# CrawlerSch26_04_22_2.net
KiCad netlist of a schematic drawn in Altium Designer
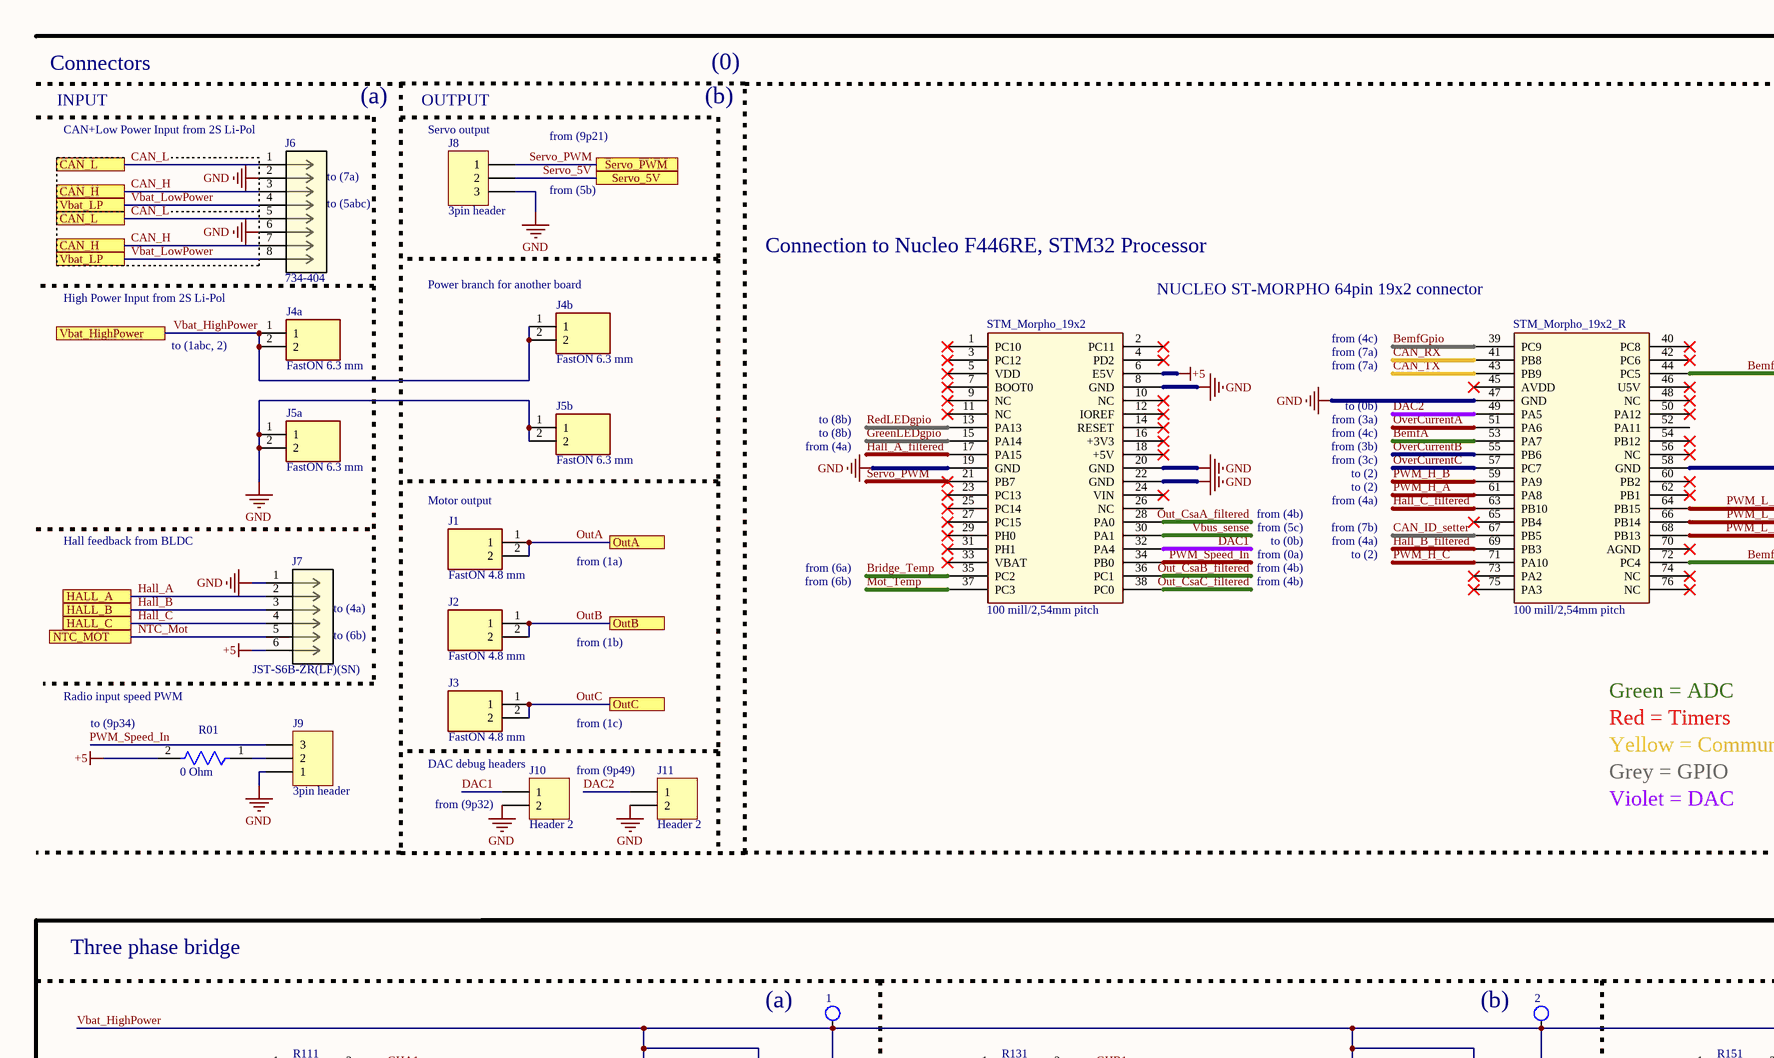
[diagram p0: CrawlerSch26_04_22 2.SchDoc, top left]
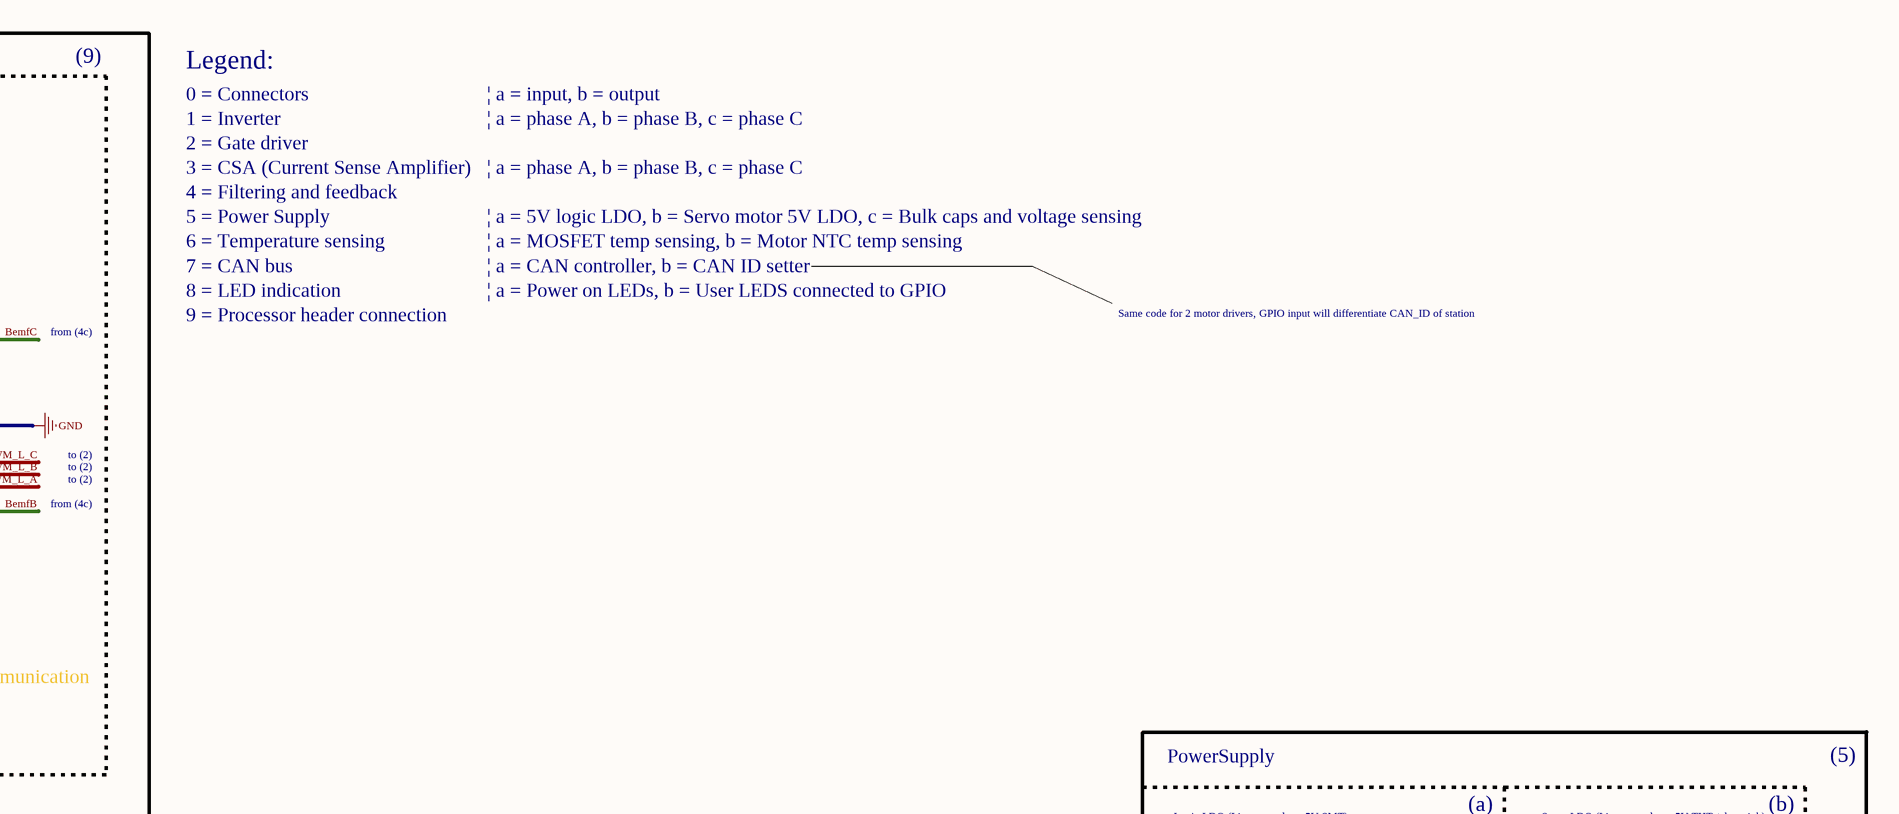
[diagram p1: CrawlerSch26_04_22 2.SchDoc, top right]
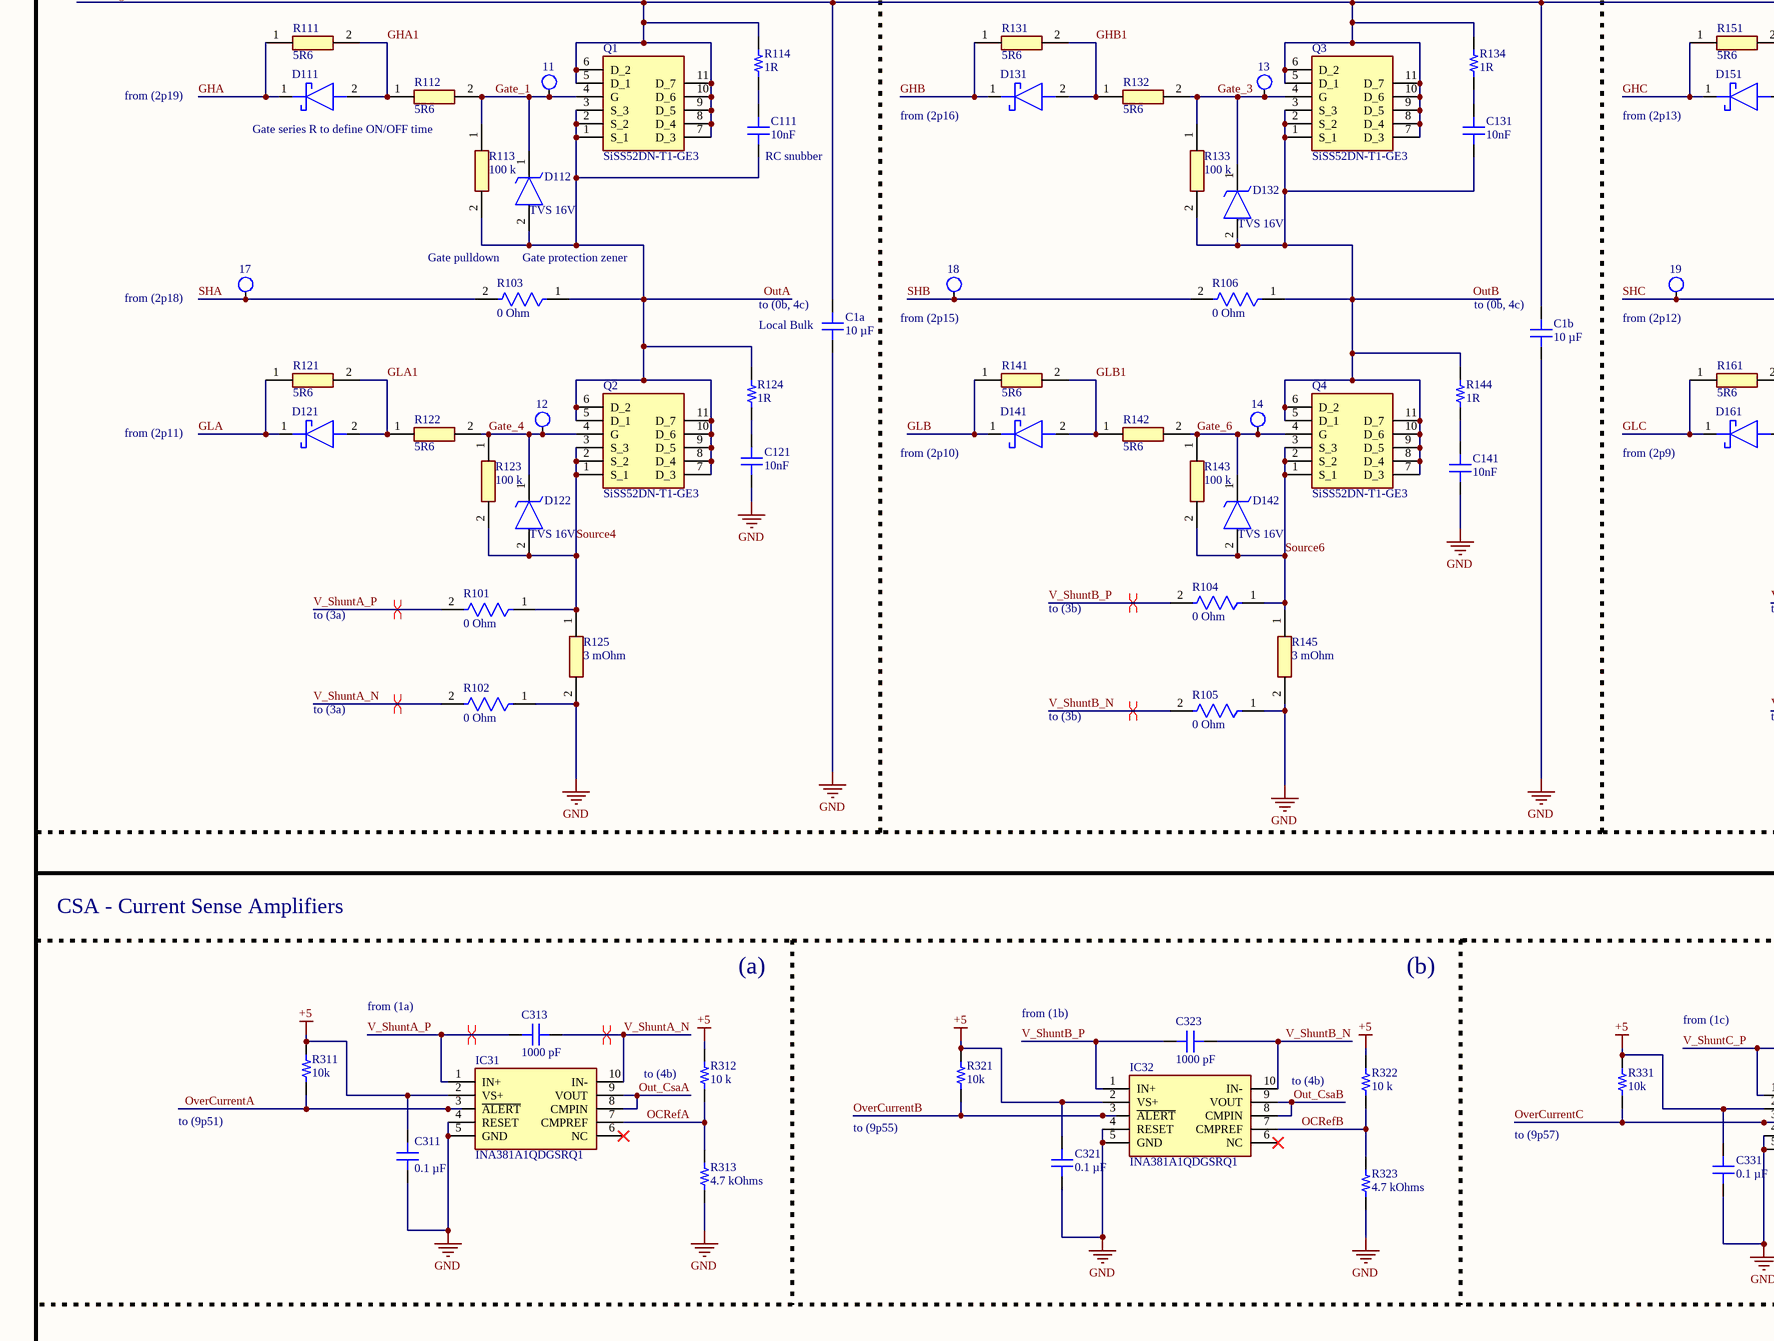
[diagram p2: CrawlerSch26_04_22 2.SchDoc, bottom left]
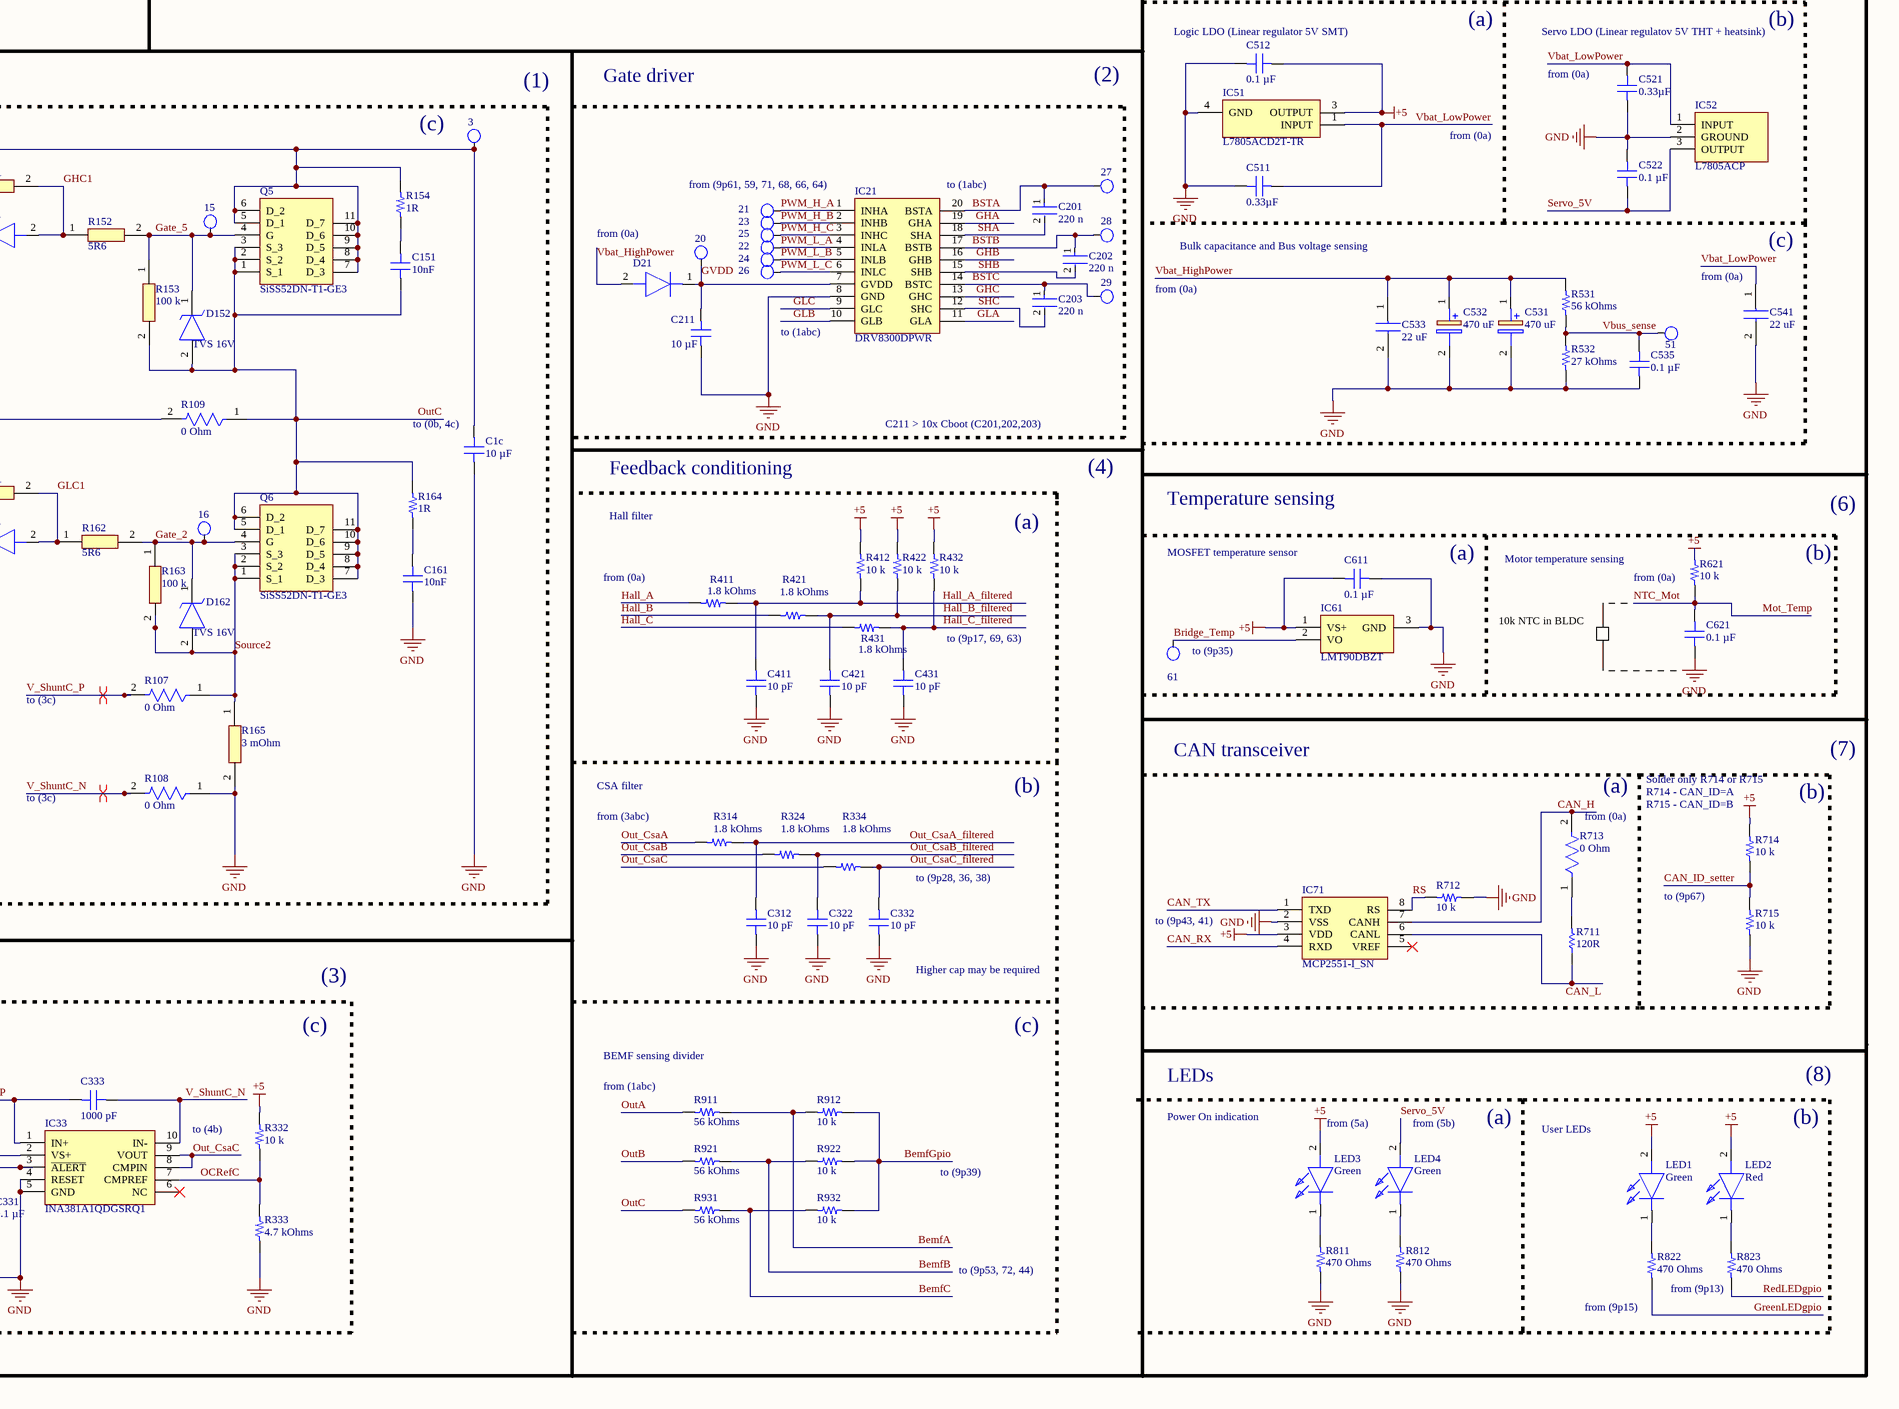
[diagram p3: CrawlerSch26_04_22 2.SchDoc, bottom right]

(export (version "E")
  (design (tool "Eeschema 10.0.6"))
  (components
    (comp (ref "1")
      (value "TestPad")
      (footprint "TestPad")
      (libsource (lib "MyLib_Crawler") (part "TestPad"))
    )
    (comp (ref "2")
      (value "TestPad")
      (footprint "TestPad")
      (libsource (lib "MyLib_Crawler") (part "TestPad"))
    )
    (comp (ref "3")
      (value "TestPad")
      (footprint "TestPad")
      (libsource (lib "MyLib_Crawler") (part "TestPad"))
    )
    (comp (ref "11")
      (value "TestPad")
      (footprint "TestPad")
      (libsource (lib "MyLib_Crawler") (part "TestPad"))
    )
    (comp (ref "12")
      (value "TestPad")
      (footprint "TestPad")
      (libsource (lib "MyLib_Crawler") (part "TestPad"))
    )
    (comp (ref "13")
      (value "TestPad")
      (footprint "TestPad")
      (libsource (lib "MyLib_Crawler") (part "TestPad"))
    )
    (comp (ref "14")
      (value "TestPad")
      (footprint "TestPad")
      (libsource (lib "MyLib_Crawler") (part "TestPad"))
    )
    (comp (ref "15")
      (value "TestPad")
      (footprint "TestPad")
      (libsource (lib "MyLib_Crawler") (part "TestPad"))
    )
    (comp (ref "16")
      (value "TestPad")
      (footprint "TestPad")
      (libsource (lib "MyLib_Crawler") (part "TestPad"))
    )
    (comp (ref "17")
      (value "TestPad")
      (footprint "TestPad")
      (libsource (lib "MyLib_Crawler") (part "TestPad"))
    )
    (comp (ref "18")
      (value "TestPad")
      (footprint "TestPad")
      (libsource (lib "MyLib_Crawler") (part "TestPad"))
    )
    (comp (ref "19")
      (value "TestPad")
      (footprint "TestPad")
      (libsource (lib "MyLib_Crawler") (part "TestPad"))
    )
    (comp (ref "20")
      (value "TestPad")
      (footprint "TestPad")
      (libsource (lib "MyLib_Crawler") (part "TestPad"))
    )
    (comp (ref "21")
      (value "TestPad")
      (footprint "TestPad")
      (libsource (lib "MyLib_Crawler") (part "TestPad"))
    )
    (comp (ref "22")
      (value "TestPad")
      (footprint "TestPad")
      (libsource (lib "MyLib_Crawler") (part "TestPad"))
    )
    (comp (ref "23")
      (value "TestPad")
      (footprint "TestPad")
      (libsource (lib "MyLib_Crawler") (part "TestPad"))
    )
    (comp (ref "24")
      (value "TestPad")
      (footprint "TestPad")
      (libsource (lib "MyLib_Crawler") (part "TestPad"))
    )
    (comp (ref "25")
      (value "TestPad")
      (footprint "TestPad")
      (libsource (lib "MyLib_Crawler") (part "TestPad"))
    )
    (comp (ref "26")
      (value "TestPad")
      (footprint "TestPad")
      (libsource (lib "MyLib_Crawler") (part "TestPad"))
    )
    (comp (ref "27")
      (value "TestPad")
      (footprint "TestPad")
      (libsource (lib "MyLib_Crawler") (part "TestPad"))
    )
    (comp (ref "28")
      (value "TestPad")
      (footprint "TestPad")
      (libsource (lib "MyLib_Crawler") (part "TestPad"))
    )
    (comp (ref "29")
      (value "TestPad")
      (footprint "TestPad")
      (libsource (lib "MyLib_Crawler") (part "TestPad"))
    )
    (comp (ref "51")
      (value "TestPad")
      (footprint "TestPad")
      (libsource (lib "MyLib_Crawler") (part "TestPad"))
    )
    (comp (ref "61")
      (value "TestPad")
      (footprint "TestPad")
      (libsource (lib "MyLib_Crawler") (part "TestPad"))
    )
    (comp (ref "C1a")
      (value "10 µF")
      (footprint "CAP 0805_2012")
      (description "CAP CER 10UF 25V X5R 0805")
      (fields (field (name "PART NUMBER") "TMK212BBJ106KG-T") (field (name "MANUFACTURER") "Taiyo Yuden"))
      (libsource (lib "Celestial Altium Library - altium_library") (part "Capacitor"))
    )
    (comp (ref "C1b")
      (value "10 µF")
      (footprint "CAP 0805_2012")
      (description "CAP CER 10UF 25V X5R 0805")
      (fields (field (name "PART NUMBER") "TMK212BBJ106KG-T") (field (name "MANUFACTURER") "Taiyo Yuden"))
      (libsource (lib "Celestial Altium Library - altium_library") (part "Capacitor"))
    )
    (comp (ref "C1c")
      (value "10 µF")
      (footprint "CAP 0805_2012")
      (description "CAP CER 10UF 25V X5R 0805")
      (fields (field (name "PART NUMBER") "TMK212BBJ106KG-T") (field (name "MANUFACTURER") "Taiyo Yuden"))
      (libsource (lib "Celestial Altium Library - altium_library") (part "Capacitor"))
    )
    (comp (ref "C111")
      (value "10nF")
      (footprint "CAP 0805_2012")
      (description "CAP CER 0805 10NF 50V C0G 5%")
      (fields (field (name "PART NUMBER") "C0805C103J5GEC7210") (field (name "MANUFACTURER") "KEMET"))
      (libsource (lib "Celestial Altium Library - altium_library") (part "Capacitor"))
    )
    (comp (ref "C121")
      (value "10nF")
      (footprint "CAP 0805_2012")
      (description "CAP CER 0805 10NF 50V C0G 5%")
      (fields (field (name "PART NUMBER") "C0805C103J5GEC7210") (field (name "MANUFACTURER") "KEMET"))
      (libsource (lib "Celestial Altium Library - altium_library") (part "Capacitor"))
    )
    (comp (ref "C131")
      (value "10nF")
      (footprint "CAP 0805_2012")
      (description "CAP CER 0805 10NF 50V C0G 5%")
      (fields (field (name "PART NUMBER") "C0805C103J5GEC7210") (field (name "MANUFACTURER") "KEMET"))
      (libsource (lib "Celestial Altium Library - altium_library") (part "Capacitor"))
    )
    (comp (ref "C141")
      (value "10nF")
      (footprint "CAP 0805_2012")
      (description "CAP CER 0805 10NF 50V C0G 5%")
      (fields (field (name "PART NUMBER") "C0805C103J5GEC7210") (field (name "MANUFACTURER") "KEMET"))
      (libsource (lib "Celestial Altium Library - altium_library") (part "Capacitor"))
    )
    (comp (ref "C151")
      (value "10nF")
      (footprint "CAP 0805_2012")
      (description "CAP CER 0805 10NF 50V C0G 5%")
      (fields (field (name "PART NUMBER") "C0805C103J5GEC7210") (field (name "MANUFACTURER") "KEMET"))
      (libsource (lib "Celestial Altium Library - altium_library") (part "Capacitor"))
    )
    (comp (ref "C161")
      (value "10nF")
      (footprint "CAP 0805_2012")
      (description "CAP CER 0805 10NF 50V C0G 5%")
      (fields (field (name "PART NUMBER") "C0805C103J5GEC7210") (field (name "MANUFACTURER") "KEMET"))
      (libsource (lib "Celestial Altium Library - altium_library") (part "Capacitor"))
    )
    (comp (ref "C201")
      (value "220 n")
      (footprint "FP-CC0603-DA-MFG")
      (description "CAP CER 0.22UF 25V X5R 0603")
      (fields
        (field (name "VOLTAGE") "25 V")
        (field (name "OCTOPART") "https://octopart.com/cc0603krx5r8bb224-yageo-29183069")
      )
      (libsource (lib "Altium Content Vault") (part "11868f565c42a9108669ba33697ecf6"))
    )
    (comp (ref "C202")
      (value "220 n")
      (footprint "FP-CC0603-DA-MFG")
      (description "CAP CER 0.22UF 25V X5R 0603")
      (fields
        (field (name "VOLTAGE") "25 V")
        (field (name "OCTOPART") "https://octopart.com/cc0603krx5r8bb224-yageo-29183069")
      )
      (libsource (lib "Altium Content Vault") (part "11868f565c42a9108669ba33697ecf6"))
    )
    (comp (ref "C203")
      (value "220 n")
      (footprint "FP-CC0603-DA-MFG")
      (description "CAP CER 0.22UF 25V X5R 0603")
      (fields
        (field (name "VOLTAGE") "25 V")
        (field (name "OCTOPART") "https://octopart.com/cc0603krx5r8bb224-yageo-29183069")
      )
      (libsource (lib "Altium Content Vault") (part "11868f565c42a9108669ba33697ecf6"))
    )
    (comp (ref "C211")
      (value "10 µF")
      (footprint "CAP 0805_2012")
      (description "CAP CER 10UF 25V X5R 0805")
      (fields (field (name "PART NUMBER") "TMK212BBJ106KG-T") (field (name "MANUFACTURER") "Taiyo Yuden"))
      (libsource (lib "Celestial Altium Library - altium_library") (part "Capacitor"))
    )
    (comp (ref "C311")
      (value "0.1 µF")
      (footprint "CAP 0805_2012")
      (description "CAP CER 0.1UF 16V X7R 0805")
      (fields (field (name "PART NUMBER") "885012207045") (field (name "MANUFACTURER") "Würth Elektronik"))
      (libsource (lib "Celestial Altium Library - altium_library") (part "Capacitor"))
    )
    (comp (ref "C312")
      (value "10 pF")
      (footprint "CAP 0805_2012")
      (description "CAP CER 10PF 16V C0G/NP0 0805")
      (fields (field (name "PART NUMBER") "885012007010") (field (name "MANUFACTURER") "Würth Elektronik"))
      (libsource (lib "Celestial Altium Library - altium_library") (part "Capacitor"))
    )
    (comp (ref "C313")
      (value "1000 pF")
      (footprint "CAP 0805_2012")
      (description "CAP CER 1000PF 16V X7R 0805")
      (fields (field (name "PART NUMBER") "885012207033") (field (name "MANUFACTURER") "Würth Elektronik"))
      (libsource (lib "Celestial Altium Library - altium_library") (part "Capacitor"))
    )
    (comp (ref "C321")
      (value "0.1 µF")
      (footprint "CAP 0805_2012")
      (description "CAP CER 0.1UF 16V X7R 0805")
      (fields (field (name "PART NUMBER") "885012207045") (field (name "MANUFACTURER") "Würth Elektronik"))
      (libsource (lib "Celestial Altium Library - altium_library") (part "Capacitor"))
    )
    (comp (ref "C322")
      (value "10 pF")
      (footprint "CAP 0805_2012")
      (description "CAP CER 10PF 16V C0G/NP0 0805")
      (fields (field (name "PART NUMBER") "885012007010") (field (name "MANUFACTURER") "Würth Elektronik"))
      (libsource (lib "Celestial Altium Library - altium_library") (part "Capacitor"))
    )
    (comp (ref "C323")
      (value "1000 pF")
      (footprint "CAP 0805_2012")
      (description "CAP CER 1000PF 16V X7R 0805")
      (fields (field (name "PART NUMBER") "885012207033") (field (name "MANUFACTURER") "Würth Elektronik"))
      (libsource (lib "Celestial Altium Library - altium_library") (part "Capacitor"))
    )
    (comp (ref "C331")
      (value "0.1 µF")
      (footprint "CAP 0805_2012")
      (description "CAP CER 0.1UF 16V X7R 0805")
      (fields (field (name "PART NUMBER") "885012207045") (field (name "MANUFACTURER") "Würth Elektronik"))
      (libsource (lib "Celestial Altium Library - altium_library") (part "Capacitor"))
    )
    (comp (ref "C332")
      (value "10 pF")
      (footprint "CAP 0805_2012")
      (description "CAP CER 10PF 16V C0G/NP0 0805")
      (fields (field (name "PART NUMBER") "885012007010") (field (name "MANUFACTURER") "Würth Elektronik"))
      (libsource (lib "Celestial Altium Library - altium_library") (part "Capacitor"))
    )
    (comp (ref "C333")
      (value "1000 pF")
      (footprint "CAP 0805_2012")
      (description "CAP CER 1000PF 16V X7R 0805")
      (fields (field (name "PART NUMBER") "885012207033") (field (name "MANUFACTURER") "Würth Elektronik"))
      (libsource (lib "Celestial Altium Library - altium_library") (part "Capacitor"))
    )
    (comp (ref "C411")
      (value "10 pF")
      (footprint "CAP 0805_2012")
      (description "CAP CER 10PF 16V C0G/NP0 0805")
      (fields (field (name "PART NUMBER") "885012007010") (field (name "MANUFACTURER") "Würth Elektronik"))
      (libsource (lib "Celestial Altium Library - altium_library") (part "Capacitor"))
    )
    (comp (ref "C421")
      (value "10 pF")
      (footprint "CAP 0805_2012")
      (description "CAP CER 10PF 16V C0G/NP0 0805")
      (fields (field (name "PART NUMBER") "885012007010") (field (name "MANUFACTURER") "Würth Elektronik"))
      (libsource (lib "Celestial Altium Library - altium_library") (part "Capacitor"))
    )
    (comp (ref "C431")
      (value "10 pF")
      (footprint "CAP 0805_2012")
      (description "CAP CER 10PF 16V C0G/NP0 0805")
      (fields (field (name "PART NUMBER") "885012007010") (field (name "MANUFACTURER") "Würth Elektronik"))
      (libsource (lib "Celestial Altium Library - altium_library") (part "Capacitor"))
    )
    (comp (ref "C511")
      (value "0.33µF")
      (footprint "CAP 0805_2012")
      (description "CAP CER 0.33UF 16V X7R 0805")
      (fields (field (name "PART NUMBER") "0805YC334JAT2A") (field (name "MANUFACTURER") "AVX Corporation"))
      (libsource (lib "Celestial Altium Library - altium_library") (part "Capacitor"))
    )
    (comp (ref "C512")
      (value "0.1 µF")
      (footprint "CAP 0805_2012")
      (description "CAP CER 0.1UF 16V X7R 0805")
      (fields (field (name "PART NUMBER") "885012207045") (field (name "MANUFACTURER") "Würth Elektronik"))
      (libsource (lib "Celestial Altium Library - altium_library") (part "Capacitor"))
    )
    (comp (ref "C521")
      (value "0.33µF")
      (footprint "CAP 0805_2012")
      (description "CAP CER 0.33UF 16V X7R 0805")
      (fields (field (name "PART NUMBER") "0805YC334JAT2A") (field (name "MANUFACTURER") "AVX Corporation"))
      (libsource (lib "Celestial Altium Library - altium_library") (part "Capacitor"))
    )
    (comp (ref "C522")
      (value "0.1 µF")
      (footprint "CAP 0805_2012")
      (description "CAP CER 0.1UF 16V X7R 0805")
      (fields (field (name "PART NUMBER") "885012207045") (field (name "MANUFACTURER") "Würth Elektronik"))
      (libsource (lib "Celestial Altium Library - altium_library") (part "Capacitor"))
    )
    (comp (ref "C531")
      (value "470 uF")
      (footprint "SamacSys:CAPPRD350W60D825H1300")
      (description "Capacitor Polarised")
      (fields (field (name "MANUFACTURER_PART_NUMBER") "RNE1C471MDN1"))
      (libsource (lib "*") (part "RNE1C471MDN1"))
    )
    (comp (ref "C532")
      (value "470 uF")
      (footprint "SamacSys:CAPPRD350W60D825H1300")
      (description "Capacitor Polarised")
      (fields (field (name "MANUFACTURER_PART_NUMBER") "RNE1C471MDN1"))
      (libsource (lib "*") (part "RNE1C471MDN1"))
    )
    (comp (ref "C533")
      (value "22 uF")
      (footprint "SamacSys:CAPC2012X145N")
      (description "Capacitor")
      (fields (field (name "MANUFACTURER_PART_NUMBER") "CL21A226MAYNNNE"))
      (libsource (lib "*") (part "CL21A226MAYNNNE"))
    )
    (comp (ref "C535")
      (value "0.1 µF")
      (footprint "CAP 0805_2012")
      (description "CAP CER 0.1UF 16V X7R 0805")
      (fields (field (name "PART NUMBER") "885012207045") (field (name "MANUFACTURER") "Würth Elektronik"))
      (libsource (lib "Celestial Altium Library - altium_library") (part "Capacitor"))
    )
    (comp (ref "C541")
      (value "22 uF")
      (footprint "SamacSys:CAPC2012X145N")
      (description "Capacitor")
      (fields (field (name "MANUFACTURER_PART_NUMBER") "CL21A226MAYNNNE"))
      (libsource (lib "*") (part "CL21A226MAYNNNE"))
    )
    (comp (ref "C611")
      (value "0.1 µF")
      (footprint "CAP 0805_2012")
      (description "CAP CER 0.1UF 16V X7R 0805")
      (fields (field (name "PART NUMBER") "885012207045") (field (name "MANUFACTURER") "Würth Elektronik"))
      (libsource (lib "Celestial Altium Library - altium_library") (part "Capacitor"))
    )
    (comp (ref "C621")
      (value "0.1 µF")
      (footprint "CAP 0805_2012")
      (description "CAP CER 0.1UF 16V X7R 0805")
      (fields (field (name "PART NUMBER") "885012207045") (field (name "MANUFACTURER") "Würth Elektronik"))
      (libsource (lib "Celestial Altium Library - altium_library") (part "Capacitor"))
    )
    (comp (ref "D21")
      (value "~")
      (footprint "SamacSys:DIOM5226X220N")
      (description "Diode")
      (fields (field (name "MANUFACTURER_PART_NUMBER") "NRVA4003T3G"))
      (libsource (lib "*") (part "NRVA4003T3G"))
    )
    (comp (ref "D111")
      (value "~")
      (footprint "SamacSys:CUHS20F30H3F")
      (description "Schottky Diode")
      (fields (field (name "MANUFACTURER_PART_NUMBER") "CUHS20F30,H3F"))
      (libsource (lib "*") (part "CUHS20F30,H3F"))
    )
    (comp (ref "D112")
      (value "TVS 16V")
      (footprint "SamacSys:SODFL1608X70N")
      (description "TVS Diode (Uni-directional)")
      (fields (field (name "MANUFACTURER_PART_NUMBER") "ESDA18-1K"))
      (libsource (lib "*") (part "ESDA18-1K"))
    )
    (comp (ref "D121")
      (value "~")
      (footprint "SamacSys:CUHS20F30H3F")
      (description "Schottky Diode")
      (fields (field (name "MANUFACTURER_PART_NUMBER") "CUHS20F30,H3F"))
      (libsource (lib "*") (part "CUHS20F30,H3F"))
    )
    (comp (ref "D122")
      (value "TVS 16V")
      (footprint "SamacSys:SODFL1608X70N")
      (description "TVS Diode (Uni-directional)")
      (fields (field (name "MANUFACTURER_PART_NUMBER") "ESDA18-1K"))
      (libsource (lib "*") (part "ESDA18-1K"))
    )
    (comp (ref "D131")
      (value "~")
      (footprint "SamacSys:CUHS20F30H3F")
      (description "Schottky Diode")
      (fields (field (name "MANUFACTURER_PART_NUMBER") "CUHS20F30,H3F"))
      (libsource (lib "*") (part "CUHS20F30,H3F"))
    )
    (comp (ref "D132")
      (value "TVS 16V")
      (footprint "SamacSys:SODFL1608X70N")
      (description "TVS Diode (Uni-directional)")
      (fields (field (name "MANUFACTURER_PART_NUMBER") "ESDA18-1K"))
      (libsource (lib "*") (part "ESDA18-1K"))
    )
    (comp (ref "D141")
      (value "~")
      (footprint "SamacSys:CUHS20F30H3F")
      (description "Schottky Diode")
      (fields (field (name "MANUFACTURER_PART_NUMBER") "CUHS20F30,H3F"))
      (libsource (lib "*") (part "CUHS20F30,H3F"))
    )
    (comp (ref "D142")
      (value "TVS 16V")
      (footprint "SamacSys:SODFL1608X70N")
      (description "TVS Diode (Uni-directional)")
      (fields (field (name "MANUFACTURER_PART_NUMBER") "ESDA18-1K"))
      (libsource (lib "*") (part "ESDA18-1K"))
    )
    (comp (ref "D151")
      (value "~")
      (footprint "SamacSys:CUHS20F30H3F")
      (description "Schottky Diode")
      (fields (field (name "MANUFACTURER_PART_NUMBER") "CUHS20F30,H3F"))
      (libsource (lib "*") (part "CUHS20F30,H3F"))
    )
    (comp (ref "D152")
      (value "TVS 16V")
      (footprint "SamacSys:SODFL1608X70N")
      (description "TVS Diode (Uni-directional)")
      (fields (field (name "MANUFACTURER_PART_NUMBER") "ESDA18-1K"))
      (libsource (lib "*") (part "ESDA18-1K"))
    )
    (comp (ref "D161")
      (value "~")
      (footprint "SamacSys:CUHS20F30H3F")
      (description "Schottky Diode")
      (fields (field (name "MANUFACTURER_PART_NUMBER") "CUHS20F30,H3F"))
      (libsource (lib "*") (part "CUHS20F30,H3F"))
    )
    (comp (ref "D162")
      (value "TVS 16V")
      (footprint "SamacSys:SODFL1608X70N")
      (description "TVS Diode (Uni-directional)")
      (fields (field (name "MANUFACTURER_PART_NUMBER") "ESDA18-1K"))
      (libsource (lib "*") (part "ESDA18-1K"))
    )
    (comp (ref "IC21")
      (value "DRV8300DPWR")
      (footprint "SamacSys:SOP65P640X120-20N")
      (description "Integrated Circuit")
      (fields (field (name "MANUFACTURER_PART_NUMBER") "DRV8300DIPWR"))
      (libsource (lib "*") (part "DRV8300DIPWR"))
    )
    (comp (ref "IC31")
      (value "INA381A1QDGSRQ1")
      (footprint "SamacSys:SOP50P490X110-10N")
      (description "Integrated Circuit")
      (libsource (lib "*") (part "INA381A1QDGSRQ1"))
    )
    (comp (ref "IC32")
      (value "INA381A1QDGSRQ1")
      (footprint "SamacSys:SOP50P490X110-10N")
      (description "Integrated Circuit")
      (libsource (lib "*") (part "INA381A1QDGSRQ1"))
    )
    (comp (ref "IC33")
      (value "INA381A1QDGSRQ1")
      (footprint "SamacSys:SOP50P490X110-10N")
      (description "Integrated Circuit")
      (libsource (lib "*") (part "INA381A1QDGSRQ1"))
    )
    (comp (ref "IC51")
      (value "L7805ACD2T-TR")
      (footprint "SamacSys:D2PAK-STB35NF10T4")
      (description "D2pak SMT")
      (libsource (lib "*") (part "L7805ACD2T-TR"))
    )
    (comp (ref "IC52")
      (value "L7805ACP")
      (footprint "SamacSys:TO255P460X1020X2030-3P")
      (description "TO-220 THT")
      (libsource (lib "*") (part "L7805ACP"))
    )
    (comp (ref "IC61")
      (value "LMT90DBZT")
      (footprint "SamacSys:SOT95P237X112-3N")
      (description "Temperature sensor")
      (libsource (lib "*") (part "LMT90DBZT"))
    )
    (comp (ref "IC71")
      (value "MCP2551-I_SN")
      (footprint "SamacSys:SOIC127P600X175-8N")
      (description "Integrated Circuit")
      (fields
        (field (name "MOUSER2 PART NUMBER") "579-MCP2551-I/SN")
        (field (name "MANUFACTURER_PART_NUMBER") "MCP2551-I/SN")
      )
      (libsource (lib "*") (part "MCP2551-I_SN"))
    )
    (comp (ref "J1")
      (value "FastON 4.8 mm")
      (footprint "SamacSys:12171561")
      (description "Motor phase A output")
      (fields (field (name "MANUFACTURER_PART_NUMBER") "1217156-1"))
      (libsource (lib "*") (part "1217156-1"))
    )
    (comp (ref "J2")
      (value "FastON 4.8 mm")
      (footprint "SamacSys:12171561")
      (description "Motor phase B output")
      (fields (field (name "MANUFACTURER_PART_NUMBER") "1217156-1"))
      (libsource (lib "*") (part "1217156-1"))
    )
    (comp (ref "J3")
      (value "FastON 4.8 mm")
      (footprint "SamacSys:12171561")
      (description "Motor phase C output")
      (fields (field (name "MANUFACTURER_PART_NUMBER") "1217156-1"))
      (libsource (lib "*") (part "1217156-1"))
    )
    (comp (ref "J4a")
      (value "FastON 6.3 mm")
      (footprint "SamacSys:7263872")
      (description "2S battery power input +")
      (fields (field (name "MANUFACTURER_PART_NUMBER") "726387-2"))
      (libsource (lib "*") (part "726387-2"))
    )
    (comp (ref "J4b")
      (value "FastON 6.3 mm")
      (footprint "SamacSys:7263872")
      (description "2S battery power input +")
      (fields (field (name "MANUFACTURER_PART_NUMBER") "726387-2"))
      (libsource (lib "*") (part "726387-2"))
    )
    (comp (ref "J5a")
      (value "FastON 6.3 mm")
      (footprint "SamacSys:7263872")
      (description "2S battery power input -")
      (fields (field (name "MANUFACTURER_PART_NUMBER") "726387-2"))
      (libsource (lib "*") (part "726387-2"))
    )
    (comp (ref "J5b")
      (value "FastON 6.3 mm")
      (footprint "SamacSys:7263872")
      (description "2S battery power input -")
      (fields (field (name "MANUFACTURER_PART_NUMBER") "726387-2"))
      (libsource (lib "*") (part "726387-2"))
    )
    (comp (ref "J6")
      (value "734-404")
      (footprint "CONN8_734-404_WAG")
      (description "No Description Available")
      (fields (field (name "COPYRIGHT") "Copyright (C) 2022 Ultra Librarian. All rights reserved."))
      (libsource (lib "734-404") (part "734-404"))
    )
    (comp (ref "J7")
      (value "JST-S6B-ZR(LF)(SN)")
      (footprint "JST-ZH-S6B")
      (libsource (lib "MyLib_Crawler") (part "JST-S6B-ZR(LF)(SN)"))
    )
    (comp (ref "J8")
      (value "3pin header")
      (footprint "HDR1X3")
      (description "Servo output power and PWM")
      (fields (field (name "PUBLISHER") "Altium Limited"))
      (libsource (lib "Miscellaneous Connectors") (part "Header 3"))
    )
    (comp (ref "J9")
      (value "3pin header")
      (footprint "HDR1X3")
      (description "Servo output power and PWM")
      (fields (field (name "PUBLISHER") "Altium Limited"))
      (libsource (lib "") (part "Header 3_1"))
    )
    (comp (ref "J10")
      (value "Header 2")
      (footprint "HDR1X2")
      (description "Header, 2-Pin")
      (fields (field (name "PUBLISHER") "Altium Limited"))
      (libsource (lib "Miscellaneous Connectors") (part "Header 2"))
    )
    (comp (ref "J11")
      (value "Header 2")
      (footprint "HDR1X2")
      (description "Header, 2-Pin")
      (fields (field (name "PUBLISHER") "Altium Limited"))
      (libsource (lib "Miscellaneous Connectors") (part "Header 2"))
    )
    (comp (ref "LED1")
      (value "Green")
      (footprint "SamacSys:LEDC1608X80N")
      (description "LED")
      (fields (field (name "MANUFACTURER_PART_NUMBER") "150060RS75000"))
      (libsource (lib "*") (part "150060RS75000"))
    )
    (comp (ref "LED2")
      (value "Red")
      (footprint "SamacSys:LEDC1608X80N")
      (description "LED")
      (fields (field (name "MANUFACTURER_PART_NUMBER") "150060RS75000"))
      (libsource (lib "*") (part "150060RS75000"))
    )
    (comp (ref "LED3")
      (value "Green")
      (footprint "SamacSys:LEDC1608X80N")
      (description "LED")
      (fields (field (name "MANUFACTURER_PART_NUMBER") "150060RS75000"))
      (libsource (lib "*") (part "150060RS75000"))
    )
    (comp (ref "LED4")
      (value "Green")
      (footprint "SamacSys:LEDC1608X80N")
      (description "LED")
      (fields (field (name "MANUFACTURER_PART_NUMBER") "150060RS75000"))
      (libsource (lib "*") (part "150060RS75000"))
    )
    (comp (ref "Q1")
      (value "SiSS52DN-T1-GE3")
      (footprint "SamacSys:SISS94DNT1GE3")
      (description "MOSFET (N-Channel)")
      (libsource (lib "*") (part "SiSS52DN-T1-GE3"))
    )
    (comp (ref "Q2")
      (value "SiSS52DN-T1-GE3")
      (footprint "SamacSys:SISS94DNT1GE3")
      (description "MOSFET (N-Channel)")
      (libsource (lib "*") (part "SiSS52DN-T1-GE3"))
    )
    (comp (ref "Q3")
      (value "SiSS52DN-T1-GE3")
      (footprint "SamacSys:SISS94DNT1GE3")
      (description "MOSFET (N-Channel)")
      (libsource (lib "*") (part "SiSS52DN-T1-GE3"))
    )
    (comp (ref "Q4")
      (value "SiSS52DN-T1-GE3")
      (footprint "SamacSys:SISS94DNT1GE3")
      (description "MOSFET (N-Channel)")
      (libsource (lib "*") (part "SiSS52DN-T1-GE3"))
    )
    (comp (ref "Q5")
      (value "SiSS52DN-T1-GE3")
      (footprint "SamacSys:SISS94DNT1GE3")
      (description "MOSFET (N-Channel)")
      (libsource (lib "*") (part "SiSS52DN-T1-GE3"))
    )
    (comp (ref "Q6")
      (value "SiSS52DN-T1-GE3")
      (footprint "SamacSys:SISS94DNT1GE3")
      (description "MOSFET (N-Channel)")
      (libsource (lib "*") (part "SiSS52DN-T1-GE3"))
    )
    (comp (ref "R01")
      (value "0 Ohm")
      (footprint "FP-CR0805-IPC_C")
      (description "Thick Film Chip Resistors 0805 0Ω 0.125W 5%")
      (fields (field (name "TOLERANCE") "5%"))
      (libsource (lib "Altium Content Vault") (part "1029c3af85768c4190bb7ad29bc67b5"))
    )
    (comp (ref "R101")
      (value "0 Ohm")
      (footprint "FP-CR0805-IPC_C")
      (description "Thick Film Chip Resistors 0805 0Ω 0.125W 5%")
      (fields (field (name "TOLERANCE") "5%"))
      (libsource (lib "Altium Content Vault") (part "1029c3af85768c4190bb7ad29bc67b5"))
    )
    (comp (ref "R102")
      (value "0 Ohm")
      (footprint "FP-CR0805-IPC_C")
      (description "Thick Film Chip Resistors 0805 0Ω 0.125W 5%")
      (fields (field (name "TOLERANCE") "5%"))
      (libsource (lib "Altium Content Vault") (part "1029c3af85768c4190bb7ad29bc67b5"))
    )
    (comp (ref "R103")
      (value "0 Ohm")
      (footprint "FP-CR0805-IPC_C")
      (description "Thick Film Chip Resistors 0805 0Ω 0.125W 5%")
      (fields (field (name "TOLERANCE") "5%"))
      (libsource (lib "Altium Content Vault") (part "1029c3af85768c4190bb7ad29bc67b5"))
    )
    (comp (ref "R104")
      (value "0 Ohm")
      (footprint "FP-CR0805-IPC_C")
      (description "Thick Film Chip Resistors 0805 0Ω 0.125W 5%")
      (fields (field (name "TOLERANCE") "5%"))
      (libsource (lib "Altium Content Vault") (part "1029c3af85768c4190bb7ad29bc67b5"))
    )
    (comp (ref "R105")
      (value "0 Ohm")
      (footprint "FP-CR0805-IPC_C")
      (description "Thick Film Chip Resistors 0805 0Ω 0.125W 5%")
      (fields (field (name "TOLERANCE") "5%"))
      (libsource (lib "Altium Content Vault") (part "1029c3af85768c4190bb7ad29bc67b5"))
    )
    (comp (ref "R106")
      (value "0 Ohm")
      (footprint "FP-CR0805-IPC_C")
      (description "Thick Film Chip Resistors 0805 0Ω 0.125W 5%")
      (fields (field (name "TOLERANCE") "5%"))
      (libsource (lib "Altium Content Vault") (part "1029c3af85768c4190bb7ad29bc67b5"))
    )
    (comp (ref "R107")
      (value "0 Ohm")
      (footprint "FP-CR0805-IPC_C")
      (description "Thick Film Chip Resistors 0805 0Ω 0.125W 5%")
      (fields (field (name "TOLERANCE") "5%"))
      (libsource (lib "Altium Content Vault") (part "1029c3af85768c4190bb7ad29bc67b5"))
    )
    (comp (ref "R108")
      (value "0 Ohm")
      (footprint "FP-CR0805-IPC_C")
      (description "Thick Film Chip Resistors 0805 0Ω 0.125W 5%")
      (fields (field (name "TOLERANCE") "5%"))
      (libsource (lib "Altium Content Vault") (part "1029c3af85768c4190bb7ad29bc67b5"))
    )
    (comp (ref "R109")
      (value "0 Ohm")
      (footprint "FP-CR0805-IPC_C")
      (description "Thick Film Chip Resistors 0805 0Ω 0.125W 5%")
      (fields (field (name "TOLERANCE") "5%"))
      (libsource (lib "Altium Content Vault") (part "1029c3af85768c4190bb7ad29bc67b5"))
    )
    (comp (ref "R111")
      (value "5R6")
      (footprint "SamacSys:ERJP06_(0805)")
      (description "Resistor")
      (fields (field (name "MANUFACTURER_PART_NUMBER") "ERJ-P06J5R6V"))
      (libsource (lib "*") (part "ERJ-P06J5R6V"))
    )
    (comp (ref "R112")
      (value "5R6")
      (footprint "SamacSys:ERJP06_(0805)")
      (description "Resistor")
      (fields (field (name "MANUFACTURER_PART_NUMBER") "ERJ-P06J5R6V"))
      (libsource (lib "*") (part "ERJ-P06J5R6V"))
    )
    (comp (ref "R113")
      (value "100 k")
      (footprint "SamacSys:RESC2012X50N")
      (description "Resistor")
      (fields (field (name "MANUFACTURER_PART_NUMBER") "CRCW0805100KJNECC"))
      (libsource (lib "*") (part "CRCW0805100KJNECC"))
    )
    (comp (ref "R114")
      (value "1R")
      (footprint "RES 0805_2012")
      (description "RES SMD 1 OHM 1% 1/3W 0805")
      (fields (field (name "PART NUMBER") "RL1220S-1R0-F") (field (name "MANUFACTURER") "Susumu"))
      (libsource (lib "Celestial Altium Library - altium_library") (part "Resistor"))
    )
    (comp (ref "R121")
      (value "5R6")
      (footprint "SamacSys:ERJP06_(0805)")
      (description "Resistor")
      (fields (field (name "MANUFACTURER_PART_NUMBER") "ERJ-P06J5R6V"))
      (libsource (lib "*") (part "ERJ-P06J5R6V"))
    )
    (comp (ref "R122")
      (value "5R6")
      (footprint "SamacSys:ERJP06_(0805)")
      (description "Resistor")
      (fields (field (name "MANUFACTURER_PART_NUMBER") "ERJ-P06J5R6V"))
      (libsource (lib "*") (part "ERJ-P06J5R6V"))
    )
    (comp (ref "R123")
      (value "100 k")
      (footprint "SamacSys:RESC2012X50N")
      (description "Resistor")
      (fields (field (name "MANUFACTURER_PART_NUMBER") "CRCW0805100KJNECC"))
      (libsource (lib "*") (part "CRCW0805100KJNECC"))
    )
    (comp (ref "R124")
      (value "1R")
      (footprint "RES 0805_2012")
      (description "RES SMD 1 OHM 1% 1/3W 0805")
      (fields (field (name "PART NUMBER") "RL1220S-1R0-F") (field (name "MANUFACTURER") "Susumu"))
      (libsource (lib "Celestial Altium Library - altium_library") (part "Resistor"))
    )
    (comp (ref "R125")
      (value "3 mOhm")
      (footprint "SamacSys:RESC6434X90N")
      (description "Resistor")
      (fields (field (name "MANUFACTURER_PART_NUMBER") "CRE2512-FZ-R002E-3"))
      (libsource (lib "*") (part "CRE2512-FZ-R002E-3"))
    )
    (comp (ref "R131")
      (value "5R6")
      (footprint "SamacSys:ERJP06_(0805)")
      (description "Resistor")
      (fields (field (name "MANUFACTURER_PART_NUMBER") "ERJ-P06J5R6V"))
      (libsource (lib "*") (part "ERJ-P06J5R6V"))
    )
    (comp (ref "R132")
      (value "5R6")
      (footprint "SamacSys:ERJP06_(0805)")
      (description "Resistor")
      (fields (field (name "MANUFACTURER_PART_NUMBER") "ERJ-P06J5R6V"))
      (libsource (lib "*") (part "ERJ-P06J5R6V"))
    )
    (comp (ref "R133")
      (value "100 k")
      (footprint "SamacSys:RESC2012X50N")
      (description "Resistor")
      (fields (field (name "MANUFACTURER_PART_NUMBER") "CRCW0805100KJNECC"))
      (libsource (lib "*") (part "CRCW0805100KJNECC"))
    )
    (comp (ref "R134")
      (value "1R")
      (footprint "RES 0805_2012")
      (description "RES SMD 1 OHM 1% 1/3W 0805")
      (fields (field (name "PART NUMBER") "RL1220S-1R0-F") (field (name "MANUFACTURER") "Susumu"))
      (libsource (lib "Celestial Altium Library - altium_library") (part "Resistor"))
    )
    (comp (ref "R141")
      (value "5R6")
      (footprint "SamacSys:ERJP06_(0805)")
      (description "Resistor")
      (fields (field (name "MANUFACTURER_PART_NUMBER") "ERJ-P06J5R6V"))
      (libsource (lib "*") (part "ERJ-P06J5R6V"))
    )
    (comp (ref "R142")
      (value "5R6")
      (footprint "SamacSys:ERJP06_(0805)")
      (description "Resistor")
      (fields (field (name "MANUFACTURER_PART_NUMBER") "ERJ-P06J5R6V"))
      (libsource (lib "*") (part "ERJ-P06J5R6V"))
    )
    (comp (ref "R143")
      (value "100 k")
      (footprint "SamacSys:RESC2012X50N")
      (description "Resistor")
      (fields (field (name "MANUFACTURER_PART_NUMBER") "CRCW0805100KJNECC"))
      (libsource (lib "*") (part "CRCW0805100KJNECC"))
    )
    (comp (ref "R144")
      (value "1R")
      (footprint "RES 0805_2012")
      (description "RES SMD 1 OHM 1% 1/3W 0805")
      (fields (field (name "PART NUMBER") "RL1220S-1R0-F") (field (name "MANUFACTURER") "Susumu"))
      (libsource (lib "Celestial Altium Library - altium_library") (part "Resistor"))
    )
    (comp (ref "R145")
      (value "3 mOhm")
      (footprint "SamacSys:RESC6434X90N")
      (description "Resistor")
      (fields (field (name "MANUFACTURER_PART_NUMBER") "CRE2512-FZ-R002E-3"))
      (libsource (lib "*") (part "CRE2512-FZ-R002E-3"))
    )
    (comp (ref "R151")
      (value "5R6")
      (footprint "SamacSys:ERJP06_(0805)")
      (description "Resistor")
      (fields (field (name "MANUFACTURER_PART_NUMBER") "ERJ-P06J5R6V"))
      (libsource (lib "*") (part "ERJ-P06J5R6V"))
    )
    (comp (ref "R152")
      (value "5R6")
      (footprint "SamacSys:ERJP06_(0805)")
      (description "Resistor")
      (fields (field (name "MANUFACTURER_PART_NUMBER") "ERJ-P06J5R6V"))
      (libsource (lib "*") (part "ERJ-P06J5R6V"))
    )
    (comp (ref "R153")
      (value "100 k")
      (footprint "SamacSys:RESC2012X50N")
      (description "Resistor")
      (fields (field (name "MANUFACTURER_PART_NUMBER") "CRCW0805100KJNECC"))
      (libsource (lib "*") (part "CRCW0805100KJNECC"))
    )
    (comp (ref "R154")
      (value "1R")
      (footprint "RES 0805_2012")
      (description "RES SMD 1 OHM 1% 1/3W 0805")
      (fields (field (name "PART NUMBER") "RL1220S-1R0-F") (field (name "MANUFACTURER") "Susumu"))
      (libsource (lib "Celestial Altium Library - altium_library") (part "Resistor"))
    )
    (comp (ref "R161")
      (value "5R6")
      (footprint "SamacSys:ERJP06_(0805)")
      (description "Resistor")
      (fields (field (name "MANUFACTURER_PART_NUMBER") "ERJ-P06J5R6V"))
      (libsource (lib "*") (part "ERJ-P06J5R6V"))
    )
    (comp (ref "R162")
      (value "5R6")
      (footprint "SamacSys:ERJP06_(0805)")
      (description "Resistor")
      (fields (field (name "MANUFACTURER_PART_NUMBER") "ERJ-P06J5R6V"))
      (libsource (lib "*") (part "ERJ-P06J5R6V"))
    )
    (comp (ref "R163")
      (value "100 k")
      (footprint "SamacSys:RESC2012X50N")
      (description "Resistor")
      (fields (field (name "MANUFACTURER_PART_NUMBER") "CRCW0805100KJNECC"))
      (libsource (lib "*") (part "CRCW0805100KJNECC"))
    )
    (comp (ref "R164")
      (value "1R")
      (footprint "RES 0805_2012")
      (description "RES SMD 1 OHM 1% 1/3W 0805")
      (fields (field (name "PART NUMBER") "RL1220S-1R0-F") (field (name "MANUFACTURER") "Susumu"))
      (libsource (lib "Celestial Altium Library - altium_library") (part "Resistor"))
    )
    (comp (ref "R165")
      (value "3 mOhm")
      (footprint "SamacSys:RESC6434X90N")
      (description "Resistor")
      (fields (field (name "MANUFACTURER_PART_NUMBER") "CRE2512-FZ-R002E-3"))
      (libsource (lib "*") (part "CRE2512-FZ-R002E-3"))
    )
    (comp (ref "R311")
      (value "10k")
      (footprint "RES 0805_2012")
      (description "RES 10K OHM 5% 1/8W 0805")
      (fields (field (name "PART NUMBER") "RC0805JR-0710KL") (field (name "MANUFACTURER") "Yageo"))
      (libsource (lib "Celestial Altium Library - altium_library") (part "Resistor"))
    )
    (comp (ref "R312")
      (value "10 k")
      (footprint "RES 0805_2012")
      (description "RES 10K OHM 1% 1/8W 0805")
      (fields (field (name "PART NUMBER") "RC0805FR-0710KL") (field (name "MANUFACTURER") "Yageo"))
      (libsource (lib "Celestial Altium Library - altium_library") (part "Resistor"))
    )
    (comp (ref "R313")
      (value "4.7 kOhms")
      (footprint "RES 0805_2012")
      (description "RES SMD 4.7K OHM 1% 1/8W 0805")
      (fields (field (name "PART NUMBER") "RC0805FR-074K7P") (field (name "MANUFACTURER") "Yageo"))
      (libsource (lib "Celestial Altium Library - altium_library") (part "Resistor"))
    )
    (comp (ref "R314")
      (value "1.8 kOhms")
      (footprint "RES 0805_2012")
      (description "RES 1.8K OHM 1% 1/8W 0805")
      (fields (field (name "PART NUMBER") "RC0805FR-071K8L") (field (name "MANUFACTURER") "Yageo"))
      (libsource (lib "Celestial Altium Library - altium_library") (part "Resistor"))
    )
    (comp (ref "R321")
      (value "10k")
      (footprint "RES 0805_2012")
      (description "RES 10K OHM 5% 1/8W 0805")
      (fields (field (name "PART NUMBER") "RC0805JR-0710KL") (field (name "MANUFACTURER") "Yageo"))
      (libsource (lib "Celestial Altium Library - altium_library") (part "Resistor"))
    )
    (comp (ref "R322")
      (value "10 k")
      (footprint "RES 0805_2012")
      (description "RES 10K OHM 1% 1/8W 0805")
      (fields (field (name "PART NUMBER") "RC0805FR-0710KL") (field (name "MANUFACTURER") "Yageo"))
      (libsource (lib "Celestial Altium Library - altium_library") (part "Resistor"))
    )
    (comp (ref "R323")
      (value "4.7 kOhms")
      (footprint "RES 0805_2012")
      (description "RES SMD 4.7K OHM 1% 1/8W 0805")
      (fields (field (name "PART NUMBER") "RC0805FR-074K7P") (field (name "MANUFACTURER") "Yageo"))
      (libsource (lib "Celestial Altium Library - altium_library") (part "Resistor"))
    )
    (comp (ref "R324")
      (value "1.8 kOhms")
      (footprint "RES 0805_2012")
      (description "RES 1.8K OHM 1% 1/8W 0805")
      (fields (field (name "PART NUMBER") "RC0805FR-071K8L") (field (name "MANUFACTURER") "Yageo"))
      (libsource (lib "Celestial Altium Library - altium_library") (part "Resistor"))
    )
    (comp (ref "R331")
      (value "10k")
      (footprint "RES 0805_2012")
      (description "RES 10K OHM 5% 1/8W 0805")
      (fields (field (name "PART NUMBER") "RC0805JR-0710KL") (field (name "MANUFACTURER") "Yageo"))
      (libsource (lib "Celestial Altium Library - altium_library") (part "Resistor"))
    )
    (comp (ref "R332")
      (value "10 k")
      (footprint "RES 0805_2012")
      (description "RES 10K OHM 1% 1/8W 0805")
      (fields (field (name "PART NUMBER") "RC0805FR-0710KL") (field (name "MANUFACTURER") "Yageo"))
      (libsource (lib "Celestial Altium Library - altium_library") (part "Resistor"))
    )
    (comp (ref "R333")
      (value "4.7 kOhms")
      (footprint "RES 0805_2012")
      (description "RES SMD 4.7K OHM 1% 1/8W 0805")
      (fields (field (name "PART NUMBER") "RC0805FR-074K7P") (field (name "MANUFACTURER") "Yageo"))
      (libsource (lib "Celestial Altium Library - altium_library") (part "Resistor"))
    )
    (comp (ref "R334")
      (value "1.8 kOhms")
      (footprint "RES 0805_2012")
      (description "RES 1.8K OHM 1% 1/8W 0805")
      (fields (field (name "PART NUMBER") "RC0805FR-071K8L") (field (name "MANUFACTURER") "Yageo"))
      (libsource (lib "Celestial Altium Library - altium_library") (part "Resistor"))
    )
    (comp (ref "R411")
      (value "1.8 kOhms")
      (footprint "RES 0805_2012")
      (description "RES 1.8K OHM 1% 1/8W 0805")
      (fields (field (name "PART NUMBER") "RC0805FR-071K8L") (field (name "MANUFACTURER") "Yageo"))
      (libsource (lib "Celestial Altium Library - altium_library") (part "Resistor"))
    )
    (comp (ref "R412")
      (value "10 k")
      (footprint "RES 0805_2012")
      (description "RES 10K OHM 1% 1/8W 0805")
      (fields (field (name "PART NUMBER") "RC0805FR-0710KL") (field (name "MANUFACTURER") "Yageo"))
      (libsource (lib "Celestial Altium Library - altium_library") (part "Resistor"))
    )
    (comp (ref "R421")
      (value "1.8 kOhms")
      (footprint "RES 0805_2012")
      (description "RES 1.8K OHM 1% 1/8W 0805")
      (fields (field (name "PART NUMBER") "RC0805FR-071K8L") (field (name "MANUFACTURER") "Yageo"))
      (libsource (lib "Celestial Altium Library - altium_library") (part "Resistor"))
    )
    (comp (ref "R422")
      (value "10 k")
      (footprint "RES 0805_2012")
      (description "RES 10K OHM 1% 1/8W 0805")
      (fields (field (name "PART NUMBER") "RC0805FR-0710KL") (field (name "MANUFACTURER") "Yageo"))
      (libsource (lib "Celestial Altium Library - altium_library") (part "Resistor"))
    )
    (comp (ref "R431")
      (value "1.8 kOhms")
      (footprint "RES 0805_2012")
      (description "RES 1.8K OHM 1% 1/8W 0805")
      (fields (field (name "PART NUMBER") "RC0805FR-071K8L") (field (name "MANUFACTURER") "Yageo"))
      (libsource (lib "Celestial Altium Library - altium_library") (part "Resistor"))
    )
    (comp (ref "R432")
      (value "10 k")
      (footprint "RES 0805_2012")
      (description "RES 10K OHM 1% 1/8W 0805")
      (fields (field (name "PART NUMBER") "RC0805FR-0710KL") (field (name "MANUFACTURER") "Yageo"))
      (libsource (lib "Celestial Altium Library - altium_library") (part "Resistor"))
    )
    (comp (ref "R531")
      (value "56 kOhms")
      (footprint "RES 0805_2012")
      (description "RES SMD 56K OHM 1% 1/8W 0805")
      (fields (field (name "PART NUMBER") "RT0805FRE0756KL") (field (name "MANUFACTURER") "Yageo"))
      (libsource (lib "Celestial Altium Library - altium_library") (part "Resistor"))
    )
    (comp (ref "R532")
      (value "27 kOhms")
      (footprint "RES 0805_2012")
      (description "RES 27K OHM 0.5% 1/8W 0805")
      (fields
        (field (name "PART NUMBER") "ERA-6AED273V")
        (field (name "MANUFACTURER") "Panasonic Electronic Components")
      )
      (libsource (lib "Celestial Altium Library - altium_library") (part "Resistor"))
    )
    (comp (ref "R621")
      (value "10 k")
      (footprint "RES 0805_2012")
      (description "RES 10K OHM 1% 1/8W 0805")
      (fields (field (name "PART NUMBER") "RC0805FR-0710KL") (field (name "MANUFACTURER") "Yageo"))
      (libsource (lib "Celestial Altium Library - altium_library") (part "Resistor"))
    )
    (comp (ref "R711")
      (value "120R")
      (footprint "RESC0805(2012)_M")
      (description "120R 0.125W 1% 0805 (2012 Metric)  SMD")
      (fields (field (name "TOLERANCE") "1 %") (field (name "POWER") "0.125 W"))
      (libsource (lib "Altium Content Vault") (part "RES"))
    )
    (comp (ref "R712")
      (value "10 k")
      (footprint "RES 0805_2012")
      (description "RES 10K OHM 1% 1/8W 0805")
      (fields (field (name "PART NUMBER") "RC0805FR-0710KL") (field (name "MANUFACTURER") "Yageo"))
      (libsource (lib "Celestial Altium Library - altium_library") (part "Resistor"))
    )
    (comp (ref "R713")
      (value "0 Ohm")
      (footprint "FP-CR0805-IPC_C")
      (description "Thick Film Chip Resistors 0805 0Ω 0.125W 5%")
      (fields (field (name "TOLERANCE") "5%"))
      (libsource (lib "Altium Content Vault") (part "1029c3af85768c4190bb7ad29bc67b5"))
    )
    (comp (ref "R714")
      (value "10 k")
      (footprint "RES 0805_2012")
      (description "RES 10K OHM 1% 1/8W 0805")
      (fields (field (name "PART NUMBER") "RC0805FR-0710KL") (field (name "MANUFACTURER") "Yageo"))
      (libsource (lib "Celestial Altium Library - altium_library") (part "Resistor"))
    )
    (comp (ref "R715")
      (value "10 k")
      (footprint "RES 0805_2012")
      (description "RES 10K OHM 1% 1/8W 0805")
      (fields (field (name "PART NUMBER") "RC0805FR-0710KL") (field (name "MANUFACTURER") "Yageo"))
      (libsource (lib "Celestial Altium Library - altium_library") (part "Resistor"))
    )
    (comp (ref "R811")
      (value "470 Ohms")
      (footprint "RES 0805_2012")
      (description "RES SMD 470 OHM 5% 1/8W 0805")
      (fields (field (name "PART NUMBER") "CR0805-JW-471ELF") (field (name "MANUFACTURER") "Bourns Inc."))
      (libsource (lib "Celestial Altium Library - altium_library") (part "Resistor"))
    )
    (comp (ref "R812")
      (value "470 Ohms")
      (footprint "RES 0805_2012")
      (description "RES SMD 470 OHM 5% 1/8W 0805")
      (fields (field (name "PART NUMBER") "CR0805-JW-471ELF") (field (name "MANUFACTURER") "Bourns Inc."))
      (libsource (lib "Celestial Altium Library - altium_library") (part "Resistor"))
    )
    (comp (ref "R822")
      (value "470 Ohms")
      (footprint "RES 0805_2012")
      (description "RES SMD 470 OHM 5% 1/8W 0805")
      (fields (field (name "PART NUMBER") "CR0805-JW-471ELF") (field (name "MANUFACTURER") "Bourns Inc."))
      (libsource (lib "Celestial Altium Library - altium_library") (part "Resistor"))
    )
    (comp (ref "R823")
      (value "470 Ohms")
      (footprint "RES 0805_2012")
      (description "RES SMD 470 OHM 5% 1/8W 0805")
      (fields (field (name "PART NUMBER") "CR0805-JW-471ELF") (field (name "MANUFACTURER") "Bourns Inc."))
      (libsource (lib "Celestial Altium Library - altium_library") (part "Resistor"))
    )
    (comp (ref "R911")
      (value "56 kOhms")
      (footprint "RES 0805_2012")
      (description "RES SMD 56K OHM 1% 1/8W 0805")
      (fields (field (name "PART NUMBER") "RT0805FRE0756KL") (field (name "MANUFACTURER") "Yageo"))
      (libsource (lib "Celestial Altium Library - altium_library") (part "Resistor"))
    )
    (comp (ref "R912")
      (value "10 k")
      (footprint "RES 0805_2012")
      (description "RES 10K OHM 1% 1/8W 0805")
      (fields (field (name "PART NUMBER") "RC0805FR-0710KL") (field (name "MANUFACTURER") "Yageo"))
      (libsource (lib "Celestial Altium Library - altium_library") (part "Resistor"))
    )
    (comp (ref "R921")
      (value "56 kOhms")
      (footprint "RES 0805_2012")
      (description "RES SMD 56K OHM 1% 1/8W 0805")
      (fields (field (name "PART NUMBER") "RT0805FRE0756KL") (field (name "MANUFACTURER") "Yageo"))
      (libsource (lib "Celestial Altium Library - altium_library") (part "Resistor"))
    )
    (comp (ref "R922")
      (value "10 k")
      (footprint "RES 0805_2012")
      (description "RES 10K OHM 1% 1/8W 0805")
      (fields (field (name "PART NUMBER") "RC0805FR-0710KL") (field (name "MANUFACTURER") "Yageo"))
      (libsource (lib "Celestial Altium Library - altium_library") (part "Resistor"))
    )
    (comp (ref "R931")
      (value "56 kOhms")
      (footprint "RES 0805_2012")
      (description "RES SMD 56K OHM 1% 1/8W 0805")
      (fields (field (name "PART NUMBER") "RT0805FRE0756KL") (field (name "MANUFACTURER") "Yageo"))
      (libsource (lib "Celestial Altium Library - altium_library") (part "Resistor"))
    )
    (comp (ref "R932")
      (value "10 k")
      (footprint "RES 0805_2012")
      (description "RES 10K OHM 1% 1/8W 0805")
      (fields (field (name "PART NUMBER") "RC0805FR-0710KL") (field (name "MANUFACTURER") "Yageo"))
      (libsource (lib "Celestial Altium Library - altium_library") (part "Resistor"))
    )
    (comp (ref "STM_Morpho_19x2")
      (value "100 mill/2,54mm pitch")
      (footprint "STM_Morpho19x2_L")
      (libsource (lib "MyLib_Crawler") (part "MorphoConnector_L"))
    )
    (comp (ref "STM_Morpho_19x2_R")
      (value "100 mill/2,54mm pitch")
      (footprint "STM_Morpho19x2_R")
      (libsource (lib "MyLib_Crawler") (part "MorphoConnector_R"))
    )
  )
  (nets
    (net (code "1") (name "+5") (class "Default")
      (node (ref "C311") (pin "2") (pinfunction "2_2") (pintype "passive"))
      (node (ref "C321") (pin "2") (pinfunction "2_2") (pintype "passive"))
      (node (ref "C331") (pin "2") (pinfunction "2_2") (pintype "passive"))
      (node (ref "C512") (pin "2") (pinfunction "2_2") (pintype "passive"))
      (node (ref "C611") (pin "2") (pinfunction "2_2") (pintype "passive"))
      (node (ref "IC31") (pin "2") (pinfunction "VS+_2") (pintype "passive"))
      (node (ref "IC32") (pin "2") (pinfunction "VS+_2") (pintype "passive"))
      (node (ref "IC33") (pin "2") (pinfunction "VS+_2") (pintype "passive"))
      (node (ref "IC51") (pin "3") (pinfunction "OUTPUT_3") (pintype "passive"))
      (node (ref "IC61") (pin "1") (pinfunction "VS+_1") (pintype "passive"))
      (node (ref "IC71") (pin "3") (pinfunction "VDD_3") (pintype "passive"))
      (node (ref "J7") (pin "6") (pinfunction "6_6") (pintype "passive"))
      (node (ref "LED1") (pin "2") (pinfunction "A_2") (pintype "passive"))
      (node (ref "LED2") (pin "2") (pinfunction "A_2") (pintype "passive"))
      (node (ref "LED3") (pin "2") (pinfunction "A_2") (pintype "passive"))
      (node (ref "R01") (pin "2") (pinfunction "2_2") (pintype "passive"))
      (node (ref "R311") (pin "2") (pinfunction "2_2") (pintype "passive"))
      (node (ref "R312") (pin "2") (pinfunction "2_2") (pintype "passive"))
      (node (ref "R321") (pin "2") (pinfunction "2_2") (pintype "passive"))
      (node (ref "R322") (pin "2") (pinfunction "2_2") (pintype "passive"))
      (node (ref "R331") (pin "2") (pinfunction "2_2") (pintype "passive"))
      (node (ref "R332") (pin "2") (pinfunction "2_2") (pintype "passive"))
      (node (ref "R412") (pin "2") (pinfunction "2_2") (pintype "passive"))
      (node (ref "R422") (pin "2") (pinfunction "2_2") (pintype "passive"))
      (node (ref "R432") (pin "2") (pinfunction "2_2") (pintype "passive"))
      (node (ref "R621") (pin "2") (pinfunction "2_2") (pintype "passive"))
      (node (ref "R714") (pin "2") (pinfunction "2_2") (pintype "passive"))
      (node (ref "STM_Morpho_19x2") (pin "6") (pinfunction "E5V_6") (pintype "passive"))
    )
    (net (code "2") (name "/BSTA") (class "Default")
      (node (ref "27") (pin "1") (pintype "passive"))
      (node (ref "C201") (pin "1") (pinfunction "1_1") (pintype "passive"))
      (node (ref "IC21") (pin "20") (pinfunction "BSTA_20") (pintype "passive"))
    )
    (net (code "3") (name "/BSTB") (class "Default")
      (node (ref "28") (pin "1") (pintype "passive"))
      (node (ref "C202") (pin "1") (pinfunction "1_1") (pintype "passive"))
      (node (ref "IC21") (pin "17") (pinfunction "BSTB_17") (pintype "passive"))
    )
    (net (code "4") (name "/BSTC") (class "Default")
      (node (ref "29") (pin "1") (pintype "passive"))
      (node (ref "C203") (pin "1") (pinfunction "1_1") (pintype "passive"))
      (node (ref "IC21") (pin "14") (pinfunction "BSTC_14") (pintype "passive"))
    )
    (net (code "5") (name "/BemfA") (class "Default")
      (node (ref "R911") (pin "2") (pinfunction "2_2") (pintype "passive"))
      (node (ref "R912") (pin "1") (pinfunction "1_1") (pintype "passive"))
      (node (ref "STM_Morpho_19x2_R") (pin "53") (pinfunction "PA7_53") (pintype "passive"))
    )
    (net (code "6") (name "/BemfB") (class "Default")
      (node (ref "R921") (pin "2") (pinfunction "2_2") (pintype "passive"))
      (node (ref "R922") (pin "1") (pinfunction "1_1") (pintype "passive"))
      (node (ref "STM_Morpho_19x2_R") (pin "72") (pinfunction "PC4_72") (pintype "passive"))
    )
    (net (code "7") (name "/BemfC") (class "Default")
      (node (ref "R931") (pin "2") (pinfunction "2_2") (pintype "passive"))
      (node (ref "R932") (pin "1") (pinfunction "1_1") (pintype "passive"))
      (node (ref "STM_Morpho_19x2_R") (pin "44") (pinfunction "PC5_44") (pintype "passive"))
    )
    (net (code "8") (name "/BemfGpio") (class "Default")
      (node (ref "R912") (pin "2") (pinfunction "2_2") (pintype "passive"))
      (node (ref "R922") (pin "2") (pinfunction "2_2") (pintype "passive"))
      (node (ref "R932") (pin "2") (pinfunction "2_2") (pintype "passive"))
      (node (ref "STM_Morpho_19x2_R") (pin "39") (pinfunction "PC9_39") (pintype "passive"))
    )
    (net (code "9") (name "/Bridge_Temp") (class "Default")
      (node (ref "61") (pin "1") (pintype "passive"))
      (node (ref "IC61") (pin "2") (pinfunction "VO_2") (pintype "passive"))
      (node (ref "STM_Morpho_19x2") (pin "35") (pinfunction "PC2_35") (pintype "passive"))
    )
    (net (code "10") (name "/CAN_H") (class "Default")
      (node (ref "IC71") (pin "7") (pinfunction "CANH_7") (pintype "passive"))
      (node (ref "J6") (pin "3") (pinfunction "3_3") (pintype "passive"))
      (node (ref "J6") (pin "7") (pinfunction "7_7") (pintype "passive"))
      (node (ref "R713") (pin "2") (pinfunction "2_2") (pintype "passive"))
    )
    (net (code "11") (name "/CAN_ID_setter") (class "Default")
      (node (ref "R714") (pin "1") (pinfunction "1_1") (pintype "passive"))
      (node (ref "R715") (pin "2") (pinfunction "2_2") (pintype "passive"))
      (node (ref "STM_Morpho_19x2_R") (pin "67") (pinfunction "PB5_67") (pintype "passive"))
    )
    (net (code "12") (name "/CAN_L") (class "Default")
      (node (ref "IC71") (pin "6") (pinfunction "CANL_6") (pintype "passive"))
      (node (ref "J6") (pin "1") (pinfunction "1_1") (pintype "passive"))
      (node (ref "J6") (pin "5") (pinfunction "5_5") (pintype "passive"))
      (node (ref "R711") (pin "1") (pinfunction "1_1") (pintype "passive"))
    )
    (net (code "13") (name "/CAN_RX") (class "Default")
      (node (ref "IC71") (pin "4") (pinfunction "RXD_4") (pintype "passive"))
      (node (ref "STM_Morpho_19x2_R") (pin "41") (pinfunction "PB8_41") (pintype "passive"))
    )
    (net (code "14") (name "/CAN_TX") (class "Default")
      (node (ref "IC71") (pin "1") (pinfunction "TXD_1") (pintype "passive"))
      (node (ref "STM_Morpho_19x2_R") (pin "43") (pinfunction "PB9_43") (pintype "passive"))
    )
    (net (code "15") (name "/DAC1") (class "Default")
      (node (ref "J10") (pin "1") (pinfunction "1_1") (pintype "passive"))
      (node (ref "STM_Morpho_19x2") (pin "32") (pinfunction "PA4_32") (pintype "passive"))
    )
    (net (code "16") (name "/DAC2") (class "Default")
      (node (ref "J11") (pin "1") (pinfunction "1_1") (pintype "passive"))
      (node (ref "STM_Morpho_19x2_R") (pin "49") (pinfunction "PA5_49") (pintype "passive"))
    )
    (net (code "17") (name "/GHA") (class "Default")
      (node (ref "D111") (pin "1") (pinfunction "K_1") (pintype "passive"))
      (node (ref "IC21") (pin "19") (pinfunction "GHA_19") (pintype "passive"))
      (node (ref "R111") (pin "1") (pinfunction "1_1") (pintype "passive"))
    )
    (net (code "18") (name "/GHA1") (class "Default")
      (node (ref "D111") (pin "2") (pinfunction "A_2") (pintype "passive"))
      (node (ref "R111") (pin "2") (pinfunction "2_2") (pintype "passive"))
      (node (ref "R112") (pin "1") (pinfunction "1_1") (pintype "passive"))
    )
    (net (code "19") (name "/GHB") (class "Default")
      (node (ref "D131") (pin "1") (pinfunction "K_1") (pintype "passive"))
      (node (ref "IC21") (pin "16") (pinfunction "GHB_16") (pintype "passive"))
      (node (ref "R131") (pin "1") (pinfunction "1_1") (pintype "passive"))
    )
    (net (code "20") (name "/GHB1") (class "Default")
      (node (ref "D131") (pin "2") (pinfunction "A_2") (pintype "passive"))
      (node (ref "R131") (pin "2") (pinfunction "2_2") (pintype "passive"))
      (node (ref "R132") (pin "1") (pinfunction "1_1") (pintype "passive"))
    )
    (net (code "21") (name "/GHC") (class "Default")
      (node (ref "D151") (pin "1") (pinfunction "K_1") (pintype "passive"))
      (node (ref "IC21") (pin "13") (pinfunction "GHC_13") (pintype "passive"))
      (node (ref "R151") (pin "1") (pinfunction "1_1") (pintype "passive"))
    )
    (net (code "22") (name "/GHC1") (class "Default")
      (node (ref "D151") (pin "2") (pinfunction "A_2") (pintype "passive"))
      (node (ref "R151") (pin "2") (pinfunction "2_2") (pintype "passive"))
      (node (ref "R152") (pin "1") (pinfunction "1_1") (pintype "passive"))
    )
    (net (code "23") (name "/GLA") (class "Default")
      (node (ref "D121") (pin "1") (pinfunction "K_1") (pintype "passive"))
      (node (ref "IC21") (pin "11") (pinfunction "GLA_11") (pintype "passive"))
      (node (ref "R121") (pin "1") (pinfunction "1_1") (pintype "passive"))
    )
    (net (code "24") (name "/GLA1") (class "Default")
      (node (ref "D121") (pin "2") (pinfunction "A_2") (pintype "passive"))
      (node (ref "R121") (pin "2") (pinfunction "2_2") (pintype "passive"))
      (node (ref "R122") (pin "1") (pinfunction "1_1") (pintype "passive"))
    )
    (net (code "25") (name "/GLB") (class "Default")
      (node (ref "D141") (pin "1") (pinfunction "K_1") (pintype "passive"))
      (node (ref "IC21") (pin "10") (pinfunction "GLB_10") (pintype "passive"))
      (node (ref "R141") (pin "1") (pinfunction "1_1") (pintype "passive"))
    )
    (net (code "26") (name "/GLB1") (class "Default")
      (node (ref "D141") (pin "2") (pinfunction "A_2") (pintype "passive"))
      (node (ref "R141") (pin "2") (pinfunction "2_2") (pintype "passive"))
      (node (ref "R142") (pin "1") (pinfunction "1_1") (pintype "passive"))
    )
    (net (code "27") (name "/GLC") (class "Default")
      (node (ref "D161") (pin "1") (pinfunction "K_1") (pintype "passive"))
      (node (ref "IC21") (pin "9") (pinfunction "GLC_9") (pintype "passive"))
      (node (ref "R161") (pin "1") (pinfunction "1_1") (pintype "passive"))
    )
    (net (code "28") (name "/GLC1") (class "Default")
      (node (ref "D161") (pin "2") (pinfunction "A_2") (pintype "passive"))
      (node (ref "R161") (pin "2") (pinfunction "2_2") (pintype "passive"))
      (node (ref "R162") (pin "1") (pinfunction "1_1") (pintype "passive"))
    )
    (net (code "29") (name "/GVDD") (class "Default")
      (node (ref "20") (pin "1") (pintype "passive"))
      (node (ref "C211") (pin "1") (pinfunction "1_1") (pintype "passive"))
      (node (ref "D21") (pin "1") (pinfunction "K_1") (pintype "passive"))
      (node (ref "IC21") (pin "7") (pinfunction "GVDD_7") (pintype "passive"))
    )
    (net (code "30") (name "/Gate_1") (class "Default")
      (node (ref "11") (pin "1") (pintype "passive"))
      (node (ref "D112") (pin "1") (pinfunction "K_1") (pintype "passive"))
      (node (ref "Q1") (pin "4") (pinfunction "G_4") (pintype "passive"))
      (node (ref "R112") (pin "2") (pinfunction "2_2") (pintype "passive"))
      (node (ref "R113") (pin "1") (pinfunction "1_1") (pintype "passive"))
    )
    (net (code "31") (name "/Gate_2") (class "Default")
      (node (ref "16") (pin "1") (pintype "passive"))
      (node (ref "D162") (pin "1") (pinfunction "K_1") (pintype "passive"))
      (node (ref "Q6") (pin "4") (pinfunction "G_4") (pintype "passive"))
      (node (ref "R162") (pin "2") (pinfunction "2_2") (pintype "passive"))
      (node (ref "R163") (pin "1") (pinfunction "1_1") (pintype "passive"))
    )
    (net (code "32") (name "/Gate_3") (class "Default")
      (node (ref "13") (pin "1") (pintype "passive"))
      (node (ref "D132") (pin "1") (pinfunction "K_1") (pintype "passive"))
      (node (ref "Q3") (pin "4") (pinfunction "G_4") (pintype "passive"))
      (node (ref "R132") (pin "2") (pinfunction "2_2") (pintype "passive"))
      (node (ref "R133") (pin "1") (pinfunction "1_1") (pintype "passive"))
    )
    (net (code "33") (name "/Gate_4") (class "Default")
      (node (ref "12") (pin "1") (pintype "passive"))
      (node (ref "D122") (pin "1") (pinfunction "K_1") (pintype "passive"))
      (node (ref "Q2") (pin "4") (pinfunction "G_4") (pintype "passive"))
      (node (ref "R122") (pin "2") (pinfunction "2_2") (pintype "passive"))
      (node (ref "R123") (pin "1") (pinfunction "1_1") (pintype "passive"))
    )
    (net (code "34") (name "/Gate_5") (class "Default")
      (node (ref "15") (pin "1") (pintype "passive"))
      (node (ref "D152") (pin "1") (pinfunction "K_1") (pintype "passive"))
      (node (ref "Q5") (pin "4") (pinfunction "G_4") (pintype "passive"))
      (node (ref "R152") (pin "2") (pinfunction "2_2") (pintype "passive"))
      (node (ref "R153") (pin "1") (pinfunction "1_1") (pintype "passive"))
    )
    (net (code "35") (name "/Gate_6") (class "Default")
      (node (ref "14") (pin "1") (pintype "passive"))
      (node (ref "D142") (pin "1") (pinfunction "K_1") (pintype "passive"))
      (node (ref "Q4") (pin "4") (pinfunction "G_4") (pintype "passive"))
      (node (ref "R142") (pin "2") (pinfunction "2_2") (pintype "passive"))
      (node (ref "R143") (pin "1") (pinfunction "1_1") (pintype "passive"))
    )
    (net (code "36") (name "/GreenLEDgpio") (class "Default")
      (node (ref "R822") (pin "1") (pinfunction "1_1") (pintype "passive"))
      (node (ref "STM_Morpho_19x2") (pin "15") (pinfunction "PA14_15") (pintype "passive"))
    )
    (net (code "37") (name "/Hall_A") (class "Default")
      (node (ref "J7") (pin "2") (pinfunction "2_2") (pintype "passive"))
      (node (ref "R411") (pin "1") (pinfunction "1_1") (pintype "passive"))
    )
    (net (code "38") (name "/Hall_A_filtered") (class "Default")
      (node (ref "C411") (pin "2") (pinfunction "2_2") (pintype "passive"))
      (node (ref "R411") (pin "2") (pinfunction "2_2") (pintype "passive"))
      (node (ref "R412") (pin "1") (pinfunction "1_1") (pintype "passive"))
      (node (ref "STM_Morpho_19x2") (pin "17") (pinfunction "PA15_17") (pintype "passive"))
    )
    (net (code "39") (name "/Hall_B") (class "Default")
      (node (ref "J7") (pin "3") (pinfunction "3_3") (pintype "passive"))
      (node (ref "R421") (pin "1") (pinfunction "1_1") (pintype "passive"))
    )
    (net (code "40") (name "/Hall_B_filtered") (class "Default")
      (node (ref "C421") (pin "2") (pinfunction "2_2") (pintype "passive"))
      (node (ref "R421") (pin "2") (pinfunction "2_2") (pintype "passive"))
      (node (ref "R422") (pin "1") (pinfunction "1_1") (pintype "passive"))
      (node (ref "STM_Morpho_19x2_R") (pin "69") (pinfunction "PB3_69") (pintype "passive"))
    )
    (net (code "41") (name "/Hall_C") (class "Default")
      (node (ref "J7") (pin "4") (pinfunction "4_4") (pintype "passive"))
      (node (ref "R431") (pin "1") (pinfunction "1_1") (pintype "passive"))
    )
    (net (code "42") (name "/Hall_C_filtered") (class "Default")
      (node (ref "C431") (pin "2") (pinfunction "2_2") (pintype "passive"))
      (node (ref "R431") (pin "2") (pinfunction "2_2") (pintype "passive"))
      (node (ref "R432") (pin "1") (pinfunction "1_1") (pintype "passive"))
      (node (ref "STM_Morpho_19x2_R") (pin "63") (pinfunction "PB10_63") (pintype "passive"))
    )
    (net (code "43") (name "/Mot_Temp") (class "Default")
      (node (ref "C621") (pin "2") (pinfunction "2_2") (pintype "passive"))
      (node (ref "J7") (pin "5") (pinfunction "5_5") (pintype "passive"))
      (node (ref "R621") (pin "1") (pinfunction "1_1") (pintype "passive"))
      (node (ref "STM_Morpho_19x2") (pin "37") (pinfunction "PC3_37") (pintype "passive"))
    )
    (net (code "44") (name "/OCRefA") (class "Default")
      (node (ref "IC31") (pin "7") (pinfunction "CMPREF_7") (pintype "passive"))
      (node (ref "R312") (pin "1") (pinfunction "1_1") (pintype "passive"))
      (node (ref "R313") (pin "2") (pinfunction "2_2") (pintype "passive"))
    )
    (net (code "45") (name "/OCRefB") (class "Default")
      (node (ref "IC32") (pin "7") (pinfunction "CMPREF_7") (pintype "passive"))
      (node (ref "R322") (pin "1") (pinfunction "1_1") (pintype "passive"))
      (node (ref "R323") (pin "2") (pinfunction "2_2") (pintype "passive"))
    )
    (net (code "46") (name "/OCRefC") (class "Default")
      (node (ref "IC33") (pin "7") (pinfunction "CMPREF_7") (pintype "passive"))
      (node (ref "R332") (pin "1") (pinfunction "1_1") (pintype "passive"))
      (node (ref "R333") (pin "2") (pinfunction "2_2") (pintype "passive"))
    )
    (net (code "47") (name "/OutA") (class "Default")
      (node (ref "C111") (pin "1") (pinfunction "1_1") (pintype "passive"))
      (node (ref "D112") (pin "2") (pinfunction "A_2") (pintype "passive"))
      (node (ref "J1") (pin "1") (pinfunction "1_1") (pintype "passive"))
      (node (ref "J1") (pin "2") (pinfunction "2_2") (pintype "passive"))
      (node (ref "Q1") (pin "1") (pinfunction "S_1_1") (pintype "passive"))
      (node (ref "Q1") (pin "2") (pinfunction "S_2_2") (pintype "passive"))
      (node (ref "Q1") (pin "3") (pinfunction "S_3_3") (pintype "passive"))
      (node (ref "Q2") (pin "10") (pinfunction "D_6_10") (pintype "passive"))
      (node (ref "Q2") (pin "11") (pinfunction "D_7_11") (pintype "passive"))
      (node (ref "Q2") (pin "5") (pinfunction "D_1_5") (pintype "passive"))
      (node (ref "Q2") (pin "6") (pinfunction "D_2_6") (pintype "passive"))
      (node (ref "Q2") (pin "7") (pinfunction "D_3_7") (pintype "passive"))
      (node (ref "Q2") (pin "8") (pinfunction "D_4_8") (pintype "passive"))
      (node (ref "Q2") (pin "9") (pinfunction "D_5_9") (pintype "passive"))
      (node (ref "R103") (pin "1") (pinfunction "1_1") (pintype "passive"))
      (node (ref "R113") (pin "2") (pinfunction "2_2") (pintype "passive"))
      (node (ref "R124") (pin "2") (pinfunction "2_2") (pintype "passive"))
      (node (ref "R911") (pin "1") (pinfunction "1_1") (pintype "passive"))
    )
    (net (code "48") (name "/OutB") (class "Default")
      (node (ref "C131") (pin "1") (pinfunction "1_1") (pintype "passive"))
      (node (ref "D132") (pin "2") (pinfunction "A_2") (pintype "passive"))
      (node (ref "J2") (pin "1") (pinfunction "1_1") (pintype "passive"))
      (node (ref "J2") (pin "2") (pinfunction "2_2") (pintype "passive"))
      (node (ref "Q3") (pin "1") (pinfunction "S_1_1") (pintype "passive"))
      (node (ref "Q3") (pin "2") (pinfunction "S_2_2") (pintype "passive"))
      (node (ref "Q3") (pin "3") (pinfunction "S_3_3") (pintype "passive"))
      (node (ref "Q4") (pin "10") (pinfunction "D_6_10") (pintype "passive"))
      (node (ref "Q4") (pin "11") (pinfunction "D_7_11") (pintype "passive"))
      (node (ref "Q4") (pin "5") (pinfunction "D_1_5") (pintype "passive"))
      (node (ref "Q4") (pin "6") (pinfunction "D_2_6") (pintype "passive"))
      (node (ref "Q4") (pin "7") (pinfunction "D_3_7") (pintype "passive"))
      (node (ref "Q4") (pin "8") (pinfunction "D_4_8") (pintype "passive"))
      (node (ref "Q4") (pin "9") (pinfunction "D_5_9") (pintype "passive"))
      (node (ref "R106") (pin "1") (pinfunction "1_1") (pintype "passive"))
      (node (ref "R133") (pin "2") (pinfunction "2_2") (pintype "passive"))
      (node (ref "R144") (pin "2") (pinfunction "2_2") (pintype "passive"))
      (node (ref "R921") (pin "1") (pinfunction "1_1") (pintype "passive"))
    )
    (net (code "49") (name "/OutC") (class "Default")
      (node (ref "C151") (pin "1") (pinfunction "1_1") (pintype "passive"))
      (node (ref "D152") (pin "2") (pinfunction "A_2") (pintype "passive"))
      (node (ref "J3") (pin "1") (pinfunction "1_1") (pintype "passive"))
      (node (ref "J3") (pin "2") (pinfunction "2_2") (pintype "passive"))
      (node (ref "Q5") (pin "1") (pinfunction "S_1_1") (pintype "passive"))
      (node (ref "Q5") (pin "2") (pinfunction "S_2_2") (pintype "passive"))
      (node (ref "Q5") (pin "3") (pinfunction "S_3_3") (pintype "passive"))
      (node (ref "Q6") (pin "10") (pinfunction "D_6_10") (pintype "passive"))
      (node (ref "Q6") (pin "11") (pinfunction "D_7_11") (pintype "passive"))
      (node (ref "Q6") (pin "5") (pinfunction "D_1_5") (pintype "passive"))
      (node (ref "Q6") (pin "6") (pinfunction "D_2_6") (pintype "passive"))
      (node (ref "Q6") (pin "7") (pinfunction "D_3_7") (pintype "passive"))
      (node (ref "Q6") (pin "8") (pinfunction "D_4_8") (pintype "passive"))
      (node (ref "Q6") (pin "9") (pinfunction "D_5_9") (pintype "passive"))
      (node (ref "R109") (pin "1") (pinfunction "1_1") (pintype "passive"))
      (node (ref "R153") (pin "2") (pinfunction "2_2") (pintype "passive"))
      (node (ref "R164") (pin "2") (pinfunction "2_2") (pintype "passive"))
      (node (ref "R931") (pin "1") (pinfunction "1_1") (pintype "passive"))
    )
    (net (code "50") (name "/Out_CsaA") (class "Default")
      (node (ref "IC31") (pin "8") (pinfunction "CMPIN_8") (pintype "passive"))
      (node (ref "IC31") (pin "9") (pinfunction "VOUT_9") (pintype "passive"))
      (node (ref "R314") (pin "1") (pinfunction "1_1") (pintype "passive"))
    )
    (net (code "51") (name "/Out_CsaA_filtered") (class "Default")
      (node (ref "C312") (pin "2") (pinfunction "2_2") (pintype "passive"))
      (node (ref "R314") (pin "2") (pinfunction "2_2") (pintype "passive"))
      (node (ref "STM_Morpho_19x2") (pin "28") (pinfunction "PA0_28") (pintype "passive"))
    )
    (net (code "52") (name "/Out_CsaB") (class "Default")
      (node (ref "IC32") (pin "8") (pinfunction "CMPIN_8") (pintype "passive"))
      (node (ref "IC32") (pin "9") (pinfunction "VOUT_9") (pintype "passive"))
      (node (ref "R324") (pin "1") (pinfunction "1_1") (pintype "passive"))
    )
    (net (code "53") (name "/Out_CsaB_filtered") (class "Default")
      (node (ref "C322") (pin "2") (pinfunction "2_2") (pintype "passive"))
      (node (ref "R324") (pin "2") (pinfunction "2_2") (pintype "passive"))
      (node (ref "STM_Morpho_19x2") (pin "36") (pinfunction "PC1_36") (pintype "passive"))
    )
    (net (code "54") (name "/Out_CsaC") (class "Default")
      (node (ref "IC33") (pin "8") (pinfunction "CMPIN_8") (pintype "passive"))
      (node (ref "IC33") (pin "9") (pinfunction "VOUT_9") (pintype "passive"))
      (node (ref "R334") (pin "1") (pinfunction "1_1") (pintype "passive"))
    )
    (net (code "55") (name "/Out_CsaC_filtered") (class "Default")
      (node (ref "C332") (pin "2") (pinfunction "2_2") (pintype "passive"))
      (node (ref "R334") (pin "2") (pinfunction "2_2") (pintype "passive"))
      (node (ref "STM_Morpho_19x2") (pin "38") (pinfunction "PC0_38") (pintype "passive"))
    )
    (net (code "56") (name "/OverCurrentA") (class "Default")
      (node (ref "IC31") (pin "3") (pinfunction "~{ALERT}_3") (pintype "passive"))
      (node (ref "R311") (pin "1") (pinfunction "1_1") (pintype "passive"))
      (node (ref "STM_Morpho_19x2_R") (pin "51") (pinfunction "PA6_51") (pintype "passive"))
    )
    (net (code "57") (name "/OverCurrentB") (class "Default")
      (node (ref "IC32") (pin "3") (pinfunction "~{ALERT}_3") (pintype "passive"))
      (node (ref "R321") (pin "1") (pinfunction "1_1") (pintype "passive"))
      (node (ref "STM_Morpho_19x2_R") (pin "55") (pinfunction "PB6_55") (pintype "passive"))
    )
    (net (code "58") (name "/OverCurrentC") (class "Default")
      (node (ref "IC33") (pin "3") (pinfunction "~{ALERT}_3") (pintype "passive"))
      (node (ref "R331") (pin "1") (pinfunction "1_1") (pintype "passive"))
      (node (ref "STM_Morpho_19x2_R") (pin "57") (pinfunction "PC7_57") (pintype "passive"))
    )
    (net (code "59") (name "/PWM_H_A") (class "Default")
      (node (ref "21") (pin "1") (pintype "passive"))
      (node (ref "IC21") (pin "1") (pinfunction "INHA_1") (pintype "passive"))
      (node (ref "STM_Morpho_19x2_R") (pin "61") (pinfunction "PA8_61") (pintype "passive"))
    )
    (net (code "60") (name "/PWM_H_B") (class "Default")
      (node (ref "23") (pin "1") (pintype "passive"))
      (node (ref "IC21") (pin "2") (pinfunction "INHB_2") (pintype "passive"))
      (node (ref "STM_Morpho_19x2_R") (pin "59") (pinfunction "PA9_59") (pintype "passive"))
    )
    (net (code "61") (name "/PWM_H_C") (class "Default")
      (node (ref "25") (pin "1") (pintype "passive"))
      (node (ref "IC21") (pin "3") (pinfunction "INHC_3") (pintype "passive"))
      (node (ref "STM_Morpho_19x2_R") (pin "71") (pinfunction "PA10_71") (pintype "passive"))
    )
    (net (code "62") (name "/PWM_L_A") (class "Default")
      (node (ref "22") (pin "1") (pintype "passive"))
      (node (ref "IC21") (pin "4") (pinfunction "INLA_4") (pintype "passive"))
      (node (ref "STM_Morpho_19x2_R") (pin "68") (pinfunction "PB13_68") (pintype "passive"))
    )
    (net (code "63") (name "/PWM_L_B") (class "Default")
      (node (ref "24") (pin "1") (pintype "passive"))
      (node (ref "IC21") (pin "5") (pinfunction "INLB_5") (pintype "passive"))
      (node (ref "STM_Morpho_19x2_R") (pin "66") (pinfunction "PB14_66") (pintype "passive"))
    )
    (net (code "64") (name "/PWM_L_C") (class "Default")
      (node (ref "26") (pin "1") (pintype "passive"))
      (node (ref "IC21") (pin "6") (pinfunction "INLC_6") (pintype "passive"))
      (node (ref "STM_Morpho_19x2_R") (pin "64") (pinfunction "PB15_64") (pintype "passive"))
    )
    (net (code "65") (name "/PWM_Speed_In") (class "Default")
      (node (ref "J9") (pin "3") (pinfunction "3_3") (pintype "passive"))
      (node (ref "STM_Morpho_19x2") (pin "34") (pinfunction "PB0_34") (pintype "passive"))
    )
    (net (code "66") (name "/RS") (class "Default")
      (node (ref "IC71") (pin "8") (pinfunction "RS_8") (pintype "passive"))
      (node (ref "R712") (pin "1") (pinfunction "1_1") (pintype "passive"))
    )
    (net (code "67") (name "/RedLEDgpio") (class "Default")
      (node (ref "R823") (pin "1") (pinfunction "1_1") (pintype "passive"))
      (node (ref "STM_Morpho_19x2") (pin "13") (pinfunction "PA13_13") (pintype "passive"))
    )
    (net (code "68") (name "/SHA") (class "Default")
      (node (ref "17") (pin "1") (pintype "passive"))
      (node (ref "C201") (pin "2") (pinfunction "2_2") (pintype "passive"))
      (node (ref "IC21") (pin "18") (pinfunction "SHA_18") (pintype "passive"))
      (node (ref "R103") (pin "2") (pinfunction "2_2") (pintype "passive"))
    )
    (net (code "69") (name "/SHB") (class "Default")
      (node (ref "18") (pin "1") (pintype "passive"))
      (node (ref "C202") (pin "2") (pinfunction "2_2") (pintype "passive"))
      (node (ref "IC21") (pin "15") (pinfunction "SHB_15") (pintype "passive"))
      (node (ref "R106") (pin "2") (pinfunction "2_2") (pintype "passive"))
    )
    (net (code "70") (name "/SHC") (class "Default")
      (node (ref "19") (pin "1") (pintype "passive"))
      (node (ref "C203") (pin "2") (pinfunction "2_2") (pintype "passive"))
      (node (ref "IC21") (pin "12") (pinfunction "SHC_12") (pintype "passive"))
      (node (ref "R109") (pin "2") (pinfunction "2_2") (pintype "passive"))
    )
    (net (code "71") (name "/Servo_5V") (class "Default")
      (node (ref "C522") (pin "1") (pinfunction "1_1") (pintype "passive"))
      (node (ref "IC52") (pin "3") (pinfunction "OUTPUT_3") (pintype "passive"))
      (node (ref "J8") (pin "2") (pinfunction "2_2") (pintype "passive"))
      (node (ref "LED4") (pin "2") (pinfunction "A_2") (pintype "passive"))
    )
    (net (code "72") (name "/Servo_PWM") (class "Default")
      (node (ref "J8") (pin "1") (pinfunction "1_1") (pintype "passive"))
      (node (ref "STM_Morpho_19x2") (pin "21") (pinfunction "PB7_21") (pintype "passive"))
    )
    (net (code "73") (name "/Source2") (class "Default")
      (node (ref "D162") (pin "2") (pinfunction "A_2") (pintype "passive"))
      (node (ref "Q6") (pin "1") (pinfunction "S_1_1") (pintype "passive"))
      (node (ref "Q6") (pin "2") (pinfunction "S_2_2") (pintype "passive"))
      (node (ref "Q6") (pin "3") (pinfunction "S_3_3") (pintype "passive"))
      (node (ref "R107") (pin "1") (pinfunction "1_1") (pintype "passive"))
      (node (ref "R163") (pin "2") (pinfunction "2_2") (pintype "passive"))
      (node (ref "R165") (pin "1") (pinfunction "1_1") (pintype "passive"))
    )
    (net (code "74") (name "/Source4") (class "Default")
      (node (ref "D122") (pin "2") (pinfunction "A_2") (pintype "passive"))
      (node (ref "Q2") (pin "1") (pinfunction "S_1_1") (pintype "passive"))
      (node (ref "Q2") (pin "2") (pinfunction "S_2_2") (pintype "passive"))
      (node (ref "Q2") (pin "3") (pinfunction "S_3_3") (pintype "passive"))
      (node (ref "R101") (pin "1") (pinfunction "1_1") (pintype "passive"))
      (node (ref "R123") (pin "2") (pinfunction "2_2") (pintype "passive"))
      (node (ref "R125") (pin "1") (pinfunction "1_1") (pintype "passive"))
    )
    (net (code "75") (name "/Source6") (class "Default")
      (node (ref "D142") (pin "2") (pinfunction "A_2") (pintype "passive"))
      (node (ref "Q4") (pin "1") (pinfunction "S_1_1") (pintype "passive"))
      (node (ref "Q4") (pin "2") (pinfunction "S_2_2") (pintype "passive"))
      (node (ref "Q4") (pin "3") (pinfunction "S_3_3") (pintype "passive"))
      (node (ref "R104") (pin "1") (pinfunction "1_1") (pintype "passive"))
      (node (ref "R143") (pin "2") (pinfunction "2_2") (pintype "passive"))
      (node (ref "R145") (pin "1") (pinfunction "1_1") (pintype "passive"))
    )
    (net (code "76") (name "/V_ShuntA_N") (class "Default")
      (node (ref "C313") (pin "1") (pinfunction "1_1") (pintype "passive"))
      (node (ref "IC31") (pin "10") (pinfunction "IN-_10") (pintype "passive"))
      (node (ref "R102") (pin "2") (pinfunction "2_2") (pintype "passive"))
    )
    (net (code "77") (name "/V_ShuntA_P") (class "Default")
      (node (ref "C313") (pin "2") (pinfunction "2_2") (pintype "passive"))
      (node (ref "IC31") (pin "1") (pinfunction "IN+_1") (pintype "passive"))
      (node (ref "R101") (pin "2") (pinfunction "2_2") (pintype "passive"))
    )
    (net (code "78") (name "/V_ShuntB_N") (class "Default")
      (node (ref "C323") (pin "1") (pinfunction "1_1") (pintype "passive"))
      (node (ref "IC32") (pin "10") (pinfunction "IN-_10") (pintype "passive"))
      (node (ref "R105") (pin "2") (pinfunction "2_2") (pintype "passive"))
    )
    (net (code "79") (name "/V_ShuntB_P") (class "Default")
      (node (ref "C323") (pin "2") (pinfunction "2_2") (pintype "passive"))
      (node (ref "IC32") (pin "1") (pinfunction "IN+_1") (pintype "passive"))
      (node (ref "R104") (pin "2") (pinfunction "2_2") (pintype "passive"))
    )
    (net (code "80") (name "/V_ShuntC_N") (class "Default")
      (node (ref "C333") (pin "1") (pinfunction "1_1") (pintype "passive"))
      (node (ref "IC33") (pin "10") (pinfunction "IN-_10") (pintype "passive"))
      (node (ref "R108") (pin "2") (pinfunction "2_2") (pintype "passive"))
    )
    (net (code "81") (name "/V_ShuntC_P") (class "Default")
      (node (ref "C333") (pin "2") (pinfunction "2_2") (pintype "passive"))
      (node (ref "IC33") (pin "1") (pinfunction "IN+_1") (pintype "passive"))
      (node (ref "R107") (pin "2") (pinfunction "2_2") (pintype "passive"))
    )
    (net (code "82") (name "/Vbat_HighPower") (class "Default")
      (node (ref "1") (pin "1") (pintype "passive"))
      (node (ref "2") (pin "1") (pintype "passive"))
      (node (ref "3") (pin "1") (pintype "passive"))
      (node (ref "C1a") (pin "2") (pinfunction "2_2") (pintype "passive"))
      (node (ref "C1b") (pin "2") (pinfunction "2_2") (pintype "passive"))
      (node (ref "C1c") (pin "2") (pinfunction "2_2") (pintype "passive"))
      (node (ref "C531") (pin "1") (pinfunction "+_1") (pintype "passive"))
      (node (ref "C532") (pin "1") (pinfunction "+_1") (pintype "passive"))
      (node (ref "C533") (pin "1") (pinfunction "1_1") (pintype "passive"))
      (node (ref "D21") (pin "2") (pinfunction "A_2") (pintype "passive"))
      (node (ref "J4a") (pin "1") (pinfunction "1_1") (pintype "passive"))
      (node (ref "J4a") (pin "2") (pinfunction "2_2") (pintype "passive"))
      (node (ref "J4b") (pin "1") (pinfunction "1_1") (pintype "passive"))
      (node (ref "J4b") (pin "2") (pinfunction "2_2") (pintype "passive"))
      (node (ref "Q1") (pin "10") (pinfunction "D_6_10") (pintype "passive"))
      (node (ref "Q1") (pin "11") (pinfunction "D_7_11") (pintype "passive"))
      (node (ref "Q1") (pin "5") (pinfunction "D_1_5") (pintype "passive"))
      (node (ref "Q1") (pin "6") (pinfunction "D_2_6") (pintype "passive"))
      (node (ref "Q1") (pin "7") (pinfunction "D_3_7") (pintype "passive"))
      (node (ref "Q1") (pin "8") (pinfunction "D_4_8") (pintype "passive"))
      (node (ref "Q1") (pin "9") (pinfunction "D_5_9") (pintype "passive"))
      (node (ref "Q3") (pin "10") (pinfunction "D_6_10") (pintype "passive"))
      (node (ref "Q3") (pin "11") (pinfunction "D_7_11") (pintype "passive"))
      (node (ref "Q3") (pin "5") (pinfunction "D_1_5") (pintype "passive"))
      (node (ref "Q3") (pin "6") (pinfunction "D_2_6") (pintype "passive"))
      (node (ref "Q3") (pin "7") (pinfunction "D_3_7") (pintype "passive"))
      (node (ref "Q3") (pin "8") (pinfunction "D_4_8") (pintype "passive"))
      (node (ref "Q3") (pin "9") (pinfunction "D_5_9") (pintype "passive"))
      (node (ref "Q5") (pin "10") (pinfunction "D_6_10") (pintype "passive"))
      (node (ref "Q5") (pin "11") (pinfunction "D_7_11") (pintype "passive"))
      (node (ref "Q5") (pin "5") (pinfunction "D_1_5") (pintype "passive"))
      (node (ref "Q5") (pin "6") (pinfunction "D_2_6") (pintype "passive"))
      (node (ref "Q5") (pin "7") (pinfunction "D_3_7") (pintype "passive"))
      (node (ref "Q5") (pin "8") (pinfunction "D_4_8") (pintype "passive"))
      (node (ref "Q5") (pin "9") (pinfunction "D_5_9") (pintype "passive"))
      (node (ref "R114") (pin "2") (pinfunction "2_2") (pintype "passive"))
      (node (ref "R134") (pin "2") (pinfunction "2_2") (pintype "passive"))
      (node (ref "R154") (pin "2") (pinfunction "2_2") (pintype "passive"))
      (node (ref "R531") (pin "2") (pinfunction "2_2") (pintype "passive"))
    )
    (net (code "83") (name "/Vbat_LowPower") (class "Default")
      (node (ref "C511") (pin "2") (pinfunction "2_2") (pintype "passive"))
      (node (ref "C521") (pin "2") (pinfunction "2_2") (pintype "passive"))
      (node (ref "C541") (pin "1") (pinfunction "1_1") (pintype "passive"))
      (node (ref "IC51") (pin "1") (pinfunction "INPUT_1") (pintype "passive"))
      (node (ref "IC52") (pin "1") (pinfunction "INPUT_1") (pintype "passive"))
      (node (ref "J6") (pin "4") (pinfunction "4_4") (pintype "passive"))
      (node (ref "J6") (pin "8") (pinfunction "8_8") (pintype "passive"))
    )
    (net (code "84") (name "/Vbus_sense") (class "Default")
      (node (ref "51") (pin "1") (pintype "passive"))
      (node (ref "C535") (pin "2") (pinfunction "2_2") (pintype "passive"))
      (node (ref "R531") (pin "1") (pinfunction "1_1") (pintype "passive"))
      (node (ref "R532") (pin "2") (pinfunction "2_2") (pintype "passive"))
      (node (ref "STM_Morpho_19x2") (pin "30") (pinfunction "PA1_30") (pintype "passive"))
    )
    (net (code "85") (name "GND") (class "Default")
      (node (ref "C121") (pin "1") (pinfunction "1_1") (pintype "passive"))
      (node (ref "C141") (pin "1") (pinfunction "1_1") (pintype "passive"))
      (node (ref "C161") (pin "1") (pinfunction "1_1") (pintype "passive"))
      (node (ref "C1a") (pin "1") (pinfunction "1_1") (pintype "passive"))
      (node (ref "C1b") (pin "1") (pinfunction "1_1") (pintype "passive"))
      (node (ref "C1c") (pin "1") (pinfunction "1_1") (pintype "passive"))
      (node (ref "C211") (pin "2") (pinfunction "2_2") (pintype "passive"))
      (node (ref "C311") (pin "1") (pinfunction "1_1") (pintype "passive"))
      (node (ref "C312") (pin "1") (pinfunction "1_1") (pintype "passive"))
      (node (ref "C321") (pin "1") (pinfunction "1_1") (pintype "passive"))
      (node (ref "C322") (pin "1") (pinfunction "1_1") (pintype "passive"))
      (node (ref "C331") (pin "1") (pinfunction "1_1") (pintype "passive"))
      (node (ref "C332") (pin "1") (pinfunction "1_1") (pintype "passive"))
      (node (ref "C411") (pin "1") (pinfunction "1_1") (pintype "passive"))
      (node (ref "C421") (pin "1") (pinfunction "1_1") (pintype "passive"))
      (node (ref "C431") (pin "1") (pinfunction "1_1") (pintype "passive"))
      (node (ref "C511") (pin "1") (pinfunction "1_1") (pintype "passive"))
      (node (ref "C512") (pin "1") (pinfunction "1_1") (pintype "passive"))
      (node (ref "C521") (pin "1") (pinfunction "1_1") (pintype "passive"))
      (node (ref "C522") (pin "2") (pinfunction "2_2") (pintype "passive"))
      (node (ref "C531") (pin "2") (pinfunction "-_2") (pintype "passive"))
      (node (ref "C532") (pin "2") (pinfunction "-_2") (pintype "passive"))
      (node (ref "C533") (pin "2") (pinfunction "2_2") (pintype "passive"))
      (node (ref "C535") (pin "1") (pinfunction "1_1") (pintype "passive"))
      (node (ref "C541") (pin "2") (pinfunction "2_2") (pintype "passive"))
      (node (ref "C611") (pin "1") (pinfunction "1_1") (pintype "passive"))
      (node (ref "C621") (pin "1") (pinfunction "1_1") (pintype "passive"))
      (node (ref "IC21") (pin "8") (pinfunction "GND_8") (pintype "passive"))
      (node (ref "IC31") (pin "4") (pinfunction "RESET_4") (pintype "passive"))
      (node (ref "IC31") (pin "5") (pinfunction "GND_5") (pintype "passive"))
      (node (ref "IC32") (pin "4") (pinfunction "RESET_4") (pintype "passive"))
      (node (ref "IC32") (pin "5") (pinfunction "GND_5") (pintype "passive"))
      (node (ref "IC33") (pin "4") (pinfunction "RESET_4") (pintype "passive"))
      (node (ref "IC33") (pin "5") (pinfunction "GND_5") (pintype "passive"))
      (node (ref "IC51") (pin "4") (pinfunction "GND_4") (pintype "power_in"))
      (node (ref "IC52") (pin "2") (pinfunction "GROUND_2") (pintype "power_in"))
      (node (ref "IC61") (pin "3") (pinfunction "GND_3") (pintype "power_in"))
      (node (ref "IC71") (pin "2") (pinfunction "VSS_2") (pintype "passive"))
      (node (ref "J10") (pin "2") (pinfunction "2_2") (pintype "passive"))
      (node (ref "J11") (pin "2") (pinfunction "2_2") (pintype "passive"))
      (node (ref "J5a") (pin "1") (pinfunction "1_1") (pintype "passive"))
      (node (ref "J5a") (pin "2") (pinfunction "2_2") (pintype "passive"))
      (node (ref "J5b") (pin "1") (pinfunction "1_1") (pintype "passive"))
      (node (ref "J5b") (pin "2") (pinfunction "2_2") (pintype "passive"))
      (node (ref "J6") (pin "2") (pinfunction "2_2") (pintype "passive"))
      (node (ref "J6") (pin "6") (pinfunction "6_6") (pintype "passive"))
      (node (ref "J7") (pin "1") (pinfunction "1_1") (pintype "passive"))
      (node (ref "J8") (pin "3") (pinfunction "3_3") (pintype "passive"))
      (node (ref "J9") (pin "1") (pinfunction "1_1") (pintype "passive"))
      (node (ref "R102") (pin "1") (pinfunction "1_1") (pintype "passive"))
      (node (ref "R105") (pin "1") (pinfunction "1_1") (pintype "passive"))
      (node (ref "R108") (pin "1") (pinfunction "1_1") (pintype "passive"))
      (node (ref "R125") (pin "2") (pinfunction "2_2") (pintype "passive"))
      (node (ref "R145") (pin "2") (pinfunction "2_2") (pintype "passive"))
      (node (ref "R165") (pin "2") (pinfunction "2_2") (pintype "passive"))
      (node (ref "R313") (pin "1") (pinfunction "1_1") (pintype "passive"))
      (node (ref "R323") (pin "1") (pinfunction "1_1") (pintype "passive"))
      (node (ref "R333") (pin "1") (pinfunction "1_1") (pintype "passive"))
      (node (ref "R532") (pin "1") (pinfunction "1_1") (pintype "passive"))
      (node (ref "R712") (pin "2") (pinfunction "2_2") (pintype "passive"))
      (node (ref "R715") (pin "1") (pinfunction "1_1") (pintype "passive"))
      (node (ref "R811") (pin "1") (pinfunction "1_1") (pintype "passive"))
      (node (ref "R812") (pin "1") (pinfunction "1_1") (pintype "passive"))
      (node (ref "STM_Morpho_19x2") (pin "19") (pinfunction "GND_19") (pintype "passive"))
      (node (ref "STM_Morpho_19x2") (pin "20") (pinfunction "GND_20") (pintype "passive"))
      (node (ref "STM_Morpho_19x2") (pin "22") (pinfunction "GND_22") (pintype "passive"))
      (node (ref "STM_Morpho_19x2") (pin "8") (pinfunction "GND_8") (pintype "passive"))
      (node (ref "STM_Morpho_19x2_R") (pin "47") (pinfunction "GND_47") (pintype "passive"))
      (node (ref "STM_Morpho_19x2_R") (pin "58") (pinfunction "GND_58") (pintype "passive"))
    )
    (net (code "86") (name "Net-(C111-Pad2)") (class "Default")
      (node (ref "C111") (pin "2") (pinfunction "2_2") (pintype "passive"))
      (node (ref "R114") (pin "1") (pinfunction "1_1") (pintype "passive"))
    )
    (net (code "87") (name "Net-(C121-Pad2)") (class "Default")
      (node (ref "C121") (pin "2") (pinfunction "2_2") (pintype "passive"))
      (node (ref "R124") (pin "1") (pinfunction "1_1") (pintype "passive"))
    )
    (net (code "88") (name "Net-(C131-Pad2)") (class "Default")
      (node (ref "C131") (pin "2") (pinfunction "2_2") (pintype "passive"))
      (node (ref "R134") (pin "1") (pinfunction "1_1") (pintype "passive"))
    )
    (net (code "89") (name "Net-(C141-Pad2)") (class "Default")
      (node (ref "C141") (pin "2") (pinfunction "2_2") (pintype "passive"))
      (node (ref "R144") (pin "1") (pinfunction "1_1") (pintype "passive"))
    )
    (net (code "90") (name "Net-(C151-Pad2)") (class "Default")
      (node (ref "C151") (pin "2") (pinfunction "2_2") (pintype "passive"))
      (node (ref "R154") (pin "1") (pinfunction "1_1") (pintype "passive"))
    )
    (net (code "91") (name "Net-(C161-Pad2)") (class "Default")
      (node (ref "C161") (pin "2") (pinfunction "2_2") (pintype "passive"))
      (node (ref "R164") (pin "1") (pinfunction "1_1") (pintype "passive"))
    )
    (net (code "92") (name "Net-(J9-Pad2)") (class "Default")
      (node (ref "J9") (pin "2") (pinfunction "2_2") (pintype "passive"))
      (node (ref "R01") (pin "1") (pinfunction "1_1") (pintype "passive"))
    )
    (net (code "93") (name "Net-(LED1-K)") (class "Default")
      (node (ref "LED1") (pin "1") (pinfunction "K_1") (pintype "passive"))
      (node (ref "R822") (pin "2") (pinfunction "2_2") (pintype "passive"))
    )
    (net (code "94") (name "Net-(LED2-K)") (class "Default")
      (node (ref "LED2") (pin "1") (pinfunction "K_1") (pintype "passive"))
      (node (ref "R823") (pin "2") (pinfunction "2_2") (pintype "passive"))
    )
    (net (code "95") (name "Net-(LED3-K)") (class "Default")
      (node (ref "LED3") (pin "1") (pinfunction "K_1") (pintype "passive"))
      (node (ref "R811") (pin "2") (pinfunction "2_2") (pintype "passive"))
    )
    (net (code "96") (name "Net-(LED4-K)") (class "Default")
      (node (ref "LED4") (pin "1") (pinfunction "K_1") (pintype "passive"))
      (node (ref "R812") (pin "2") (pinfunction "2_2") (pintype "passive"))
    )
    (net (code "97") (name "Net-(R711-Pad2)") (class "Default")
      (node (ref "R711") (pin "2") (pinfunction "2_2") (pintype "passive"))
      (node (ref "R713") (pin "1") (pinfunction "1_1") (pintype "passive"))
    )
    (net (code "98") (name "unconnected-(IC31-NC-Pad6)") (class "Default")
      (node (ref "IC31") (pin "6") (pinfunction "NC_6") (pintype "passive+no_connect"))
    )
    (net (code "99") (name "unconnected-(IC32-NC-Pad6)") (class "Default")
      (node (ref "IC32") (pin "6") (pinfunction "NC_6") (pintype "passive+no_connect"))
    )
    (net (code "100") (name "unconnected-(IC33-NC-Pad6)") (class "Default")
      (node (ref "IC33") (pin "6") (pinfunction "NC_6") (pintype "passive+no_connect"))
    )
    (net (code "101") (name "unconnected-(IC71-VREF-Pad5)") (class "Default")
      (node (ref "IC71") (pin "5") (pinfunction "VREF_5") (pintype "passive+no_connect"))
    )
    (net (code "102") (name "unconnected-(STM_Morpho_19x2-+3V3-Pad16)") (class "Default")
      (node (ref "STM_Morpho_19x2") (pin "16") (pinfunction "+3V3_16") (pintype "passive+no_connect"))
    )
    (net (code "103") (name "unconnected-(STM_Morpho_19x2-+5V-Pad18)") (class "Default")
      (node (ref "STM_Morpho_19x2") (pin "18") (pinfunction "+5V_18") (pintype "passive+no_connect"))
    )
    (net (code "104") (name "unconnected-(STM_Morpho_19x2-BOOT0-Pad7)") (class "Default")
      (node (ref "STM_Morpho_19x2") (pin "7") (pinfunction "BOOT0_7") (pintype "passive+no_connect"))
    )
    (net (code "105") (name "unconnected-(STM_Morpho_19x2-IOREF-Pad12)") (class "Default")
      (node (ref "STM_Morpho_19x2") (pin "12") (pinfunction "IOREF_12") (pintype "passive+no_connect"))
    )
    (net (code "106") (name "unconnected-(STM_Morpho_19x2-NC-Pad9)") (class "Default")
      (node (ref "STM_Morpho_19x2") (pin "9") (pinfunction "NC_9") (pintype "passive+no_connect"))
    )
    (net (code "107") (name "unconnected-(STM_Morpho_19x2-NC-Pad10)") (class "Default")
      (node (ref "STM_Morpho_19x2") (pin "10") (pinfunction "NC_10") (pintype "passive+no_connect"))
    )
    (net (code "108") (name "unconnected-(STM_Morpho_19x2-NC-Pad11)") (class "Default")
      (node (ref "STM_Morpho_19x2") (pin "11") (pinfunction "NC_11") (pintype "passive+no_connect"))
    )
    (net (code "109") (name "unconnected-(STM_Morpho_19x2-NC-Pad26)") (class "Default")
      (node (ref "STM_Morpho_19x2") (pin "26") (pinfunction "NC_26") (pintype "passive"))
    )
    (net (code "110") (name "unconnected-(STM_Morpho_19x2-PC10-Pad1)") (class "Default")
      (node (ref "STM_Morpho_19x2") (pin "1") (pinfunction "PC10_1") (pintype "passive+no_connect"))
    )
    (net (code "111") (name "unconnected-(STM_Morpho_19x2-PC11-Pad2)") (class "Default")
      (node (ref "STM_Morpho_19x2") (pin "2") (pinfunction "PC11_2") (pintype "passive+no_connect"))
    )
    (net (code "112") (name "unconnected-(STM_Morpho_19x2-PC12-Pad3)") (class "Default")
      (node (ref "STM_Morpho_19x2") (pin "3") (pinfunction "PC12_3") (pintype "passive+no_connect"))
    )
    (net (code "113") (name "unconnected-(STM_Morpho_19x2-PC13-Pad23)") (class "Default")
      (node (ref "STM_Morpho_19x2") (pin "23") (pinfunction "PC13_23") (pintype "passive+no_connect"))
    )
    (net (code "114") (name "unconnected-(STM_Morpho_19x2-PC14-Pad25)") (class "Default")
      (node (ref "STM_Morpho_19x2") (pin "25") (pinfunction "PC14_25") (pintype "passive+no_connect"))
    )
    (net (code "115") (name "unconnected-(STM_Morpho_19x2-PC15-Pad27)") (class "Default")
      (node (ref "STM_Morpho_19x2") (pin "27") (pinfunction "PC15_27") (pintype "passive+no_connect"))
    )
    (net (code "116") (name "unconnected-(STM_Morpho_19x2-PD2-Pad4)") (class "Default")
      (node (ref "STM_Morpho_19x2") (pin "4") (pinfunction "PD2_4") (pintype "passive+no_connect"))
    )
    (net (code "117") (name "unconnected-(STM_Morpho_19x2-PH0-Pad29)") (class "Default")
      (node (ref "STM_Morpho_19x2") (pin "29") (pinfunction "PH0_29") (pintype "passive+no_connect"))
    )
    (net (code "118") (name "unconnected-(STM_Morpho_19x2-PH1-Pad31)") (class "Default")
      (node (ref "STM_Morpho_19x2") (pin "31") (pinfunction "PH1_31") (pintype "passive+no_connect"))
    )
    (net (code "119") (name "unconnected-(STM_Morpho_19x2-RESET-Pad14)") (class "Default")
      (node (ref "STM_Morpho_19x2") (pin "14") (pinfunction "RESET_14") (pintype "passive+no_connect"))
    )
    (net (code "120") (name "unconnected-(STM_Morpho_19x2-VBAT-Pad33)") (class "Default")
      (node (ref "STM_Morpho_19x2") (pin "33") (pinfunction "VBAT_33") (pintype "passive+no_connect"))
    )
    (net (code "121") (name "unconnected-(STM_Morpho_19x2-VDD-Pad5)") (class "Default")
      (node (ref "STM_Morpho_19x2") (pin "5") (pinfunction "VDD_5") (pintype "passive+no_connect"))
    )
    (net (code "122") (name "unconnected-(STM_Morpho_19x2-VIN-Pad24)") (class "Default")
      (node (ref "STM_Morpho_19x2") (pin "24") (pinfunction "VIN_24") (pintype "passive+no_connect"))
    )
    (net (code "123") (name "unconnected-(STM_Morpho_19x2_R-AGND-Pad70)") (class "Default")
      (node (ref "STM_Morpho_19x2_R") (pin "70") (pinfunction "AGND_70") (pintype "passive+no_connect"))
    )
    (net (code "124") (name "unconnected-(STM_Morpho_19x2_R-AVDD-Pad45)") (class "Default")
      (node (ref "STM_Morpho_19x2_R") (pin "45") (pinfunction "AVDD_45") (pintype "passive+no_connect"))
    )
    (net (code "125") (name "unconnected-(STM_Morpho_19x2_R-NC-Pad48)") (class "Default")
      (node (ref "STM_Morpho_19x2_R") (pin "48") (pinfunction "NC_48") (pintype "passive+no_connect"))
    )
    (net (code "126") (name "unconnected-(STM_Morpho_19x2_R-NC-Pad56)") (class "Default")
      (node (ref "STM_Morpho_19x2_R") (pin "56") (pinfunction "NC_56") (pintype "passive+no_connect"))
    )
    (net (code "127") (name "unconnected-(STM_Morpho_19x2_R-NC-Pad74)") (class "Default")
      (node (ref "STM_Morpho_19x2_R") (pin "74") (pinfunction "NC_74") (pintype "passive+no_connect"))
    )
    (net (code "128") (name "unconnected-(STM_Morpho_19x2_R-NC-Pad76)") (class "Default")
      (node (ref "STM_Morpho_19x2_R") (pin "76") (pinfunction "NC_76") (pintype "passive+no_connect"))
    )
    (net (code "129") (name "unconnected-(STM_Morpho_19x2_R-PA2-Pad73)") (class "Default")
      (node (ref "STM_Morpho_19x2_R") (pin "73") (pinfunction "PA2_73") (pintype "passive+no_connect"))
    )
    (net (code "130") (name "unconnected-(STM_Morpho_19x2_R-PA3-Pad75)") (class "Default")
      (node (ref "STM_Morpho_19x2_R") (pin "75") (pinfunction "PA3_75") (pintype "passive+no_connect"))
    )
    (net (code "131") (name "unconnected-(STM_Morpho_19x2_R-PA11-Pad52)") (class "Default")
      (node (ref "STM_Morpho_19x2_R") (pin "52") (pinfunction "PA11_52") (pintype "passive"))
    )
    (net (code "132") (name "unconnected-(STM_Morpho_19x2_R-PA12-Pad50)") (class "Default")
      (node (ref "STM_Morpho_19x2_R") (pin "50") (pinfunction "PA12_50") (pintype "passive+no_connect"))
    )
    (net (code "133") (name "unconnected-(STM_Morpho_19x2_R-PB1-Pad62)") (class "Default")
      (node (ref "STM_Morpho_19x2_R") (pin "62") (pinfunction "PB1_62") (pintype "passive+no_connect"))
    )
    (net (code "134") (name "unconnected-(STM_Morpho_19x2_R-PB2-Pad60)") (class "Default")
      (node (ref "STM_Morpho_19x2_R") (pin "60") (pinfunction "PB2_60") (pintype "passive+no_connect"))
    )
    (net (code "135") (name "unconnected-(STM_Morpho_19x2_R-PB4-Pad65)") (class "Default")
      (node (ref "STM_Morpho_19x2_R") (pin "65") (pinfunction "PB4_65") (pintype "passive+no_connect"))
    )
    (net (code "136") (name "unconnected-(STM_Morpho_19x2_R-PB12-Pad54)") (class "Default")
      (node (ref "STM_Morpho_19x2_R") (pin "54") (pinfunction "PB12_54") (pintype "passive+no_connect"))
    )
    (net (code "137") (name "unconnected-(STM_Morpho_19x2_R-PC6-Pad42)") (class "Default")
      (node (ref "STM_Morpho_19x2_R") (pin "42") (pinfunction "PC6_42") (pintype "passive+no_connect"))
    )
    (net (code "138") (name "unconnected-(STM_Morpho_19x2_R-PC8-Pad40)") (class "Default")
      (node (ref "STM_Morpho_19x2_R") (pin "40") (pinfunction "PC8_40") (pintype "passive+no_connect"))
    )
    (net (code "139") (name "unconnected-(STM_Morpho_19x2_R-U5V-Pad46)") (class "Default")
      (node (ref "STM_Morpho_19x2_R") (pin "46") (pinfunction "U5V_46") (pintype "passive+no_connect"))
    )
  )
)
